# Calliope_mini_rev2_0.net
KiCad netlist of a schematic drawn in EAGLE
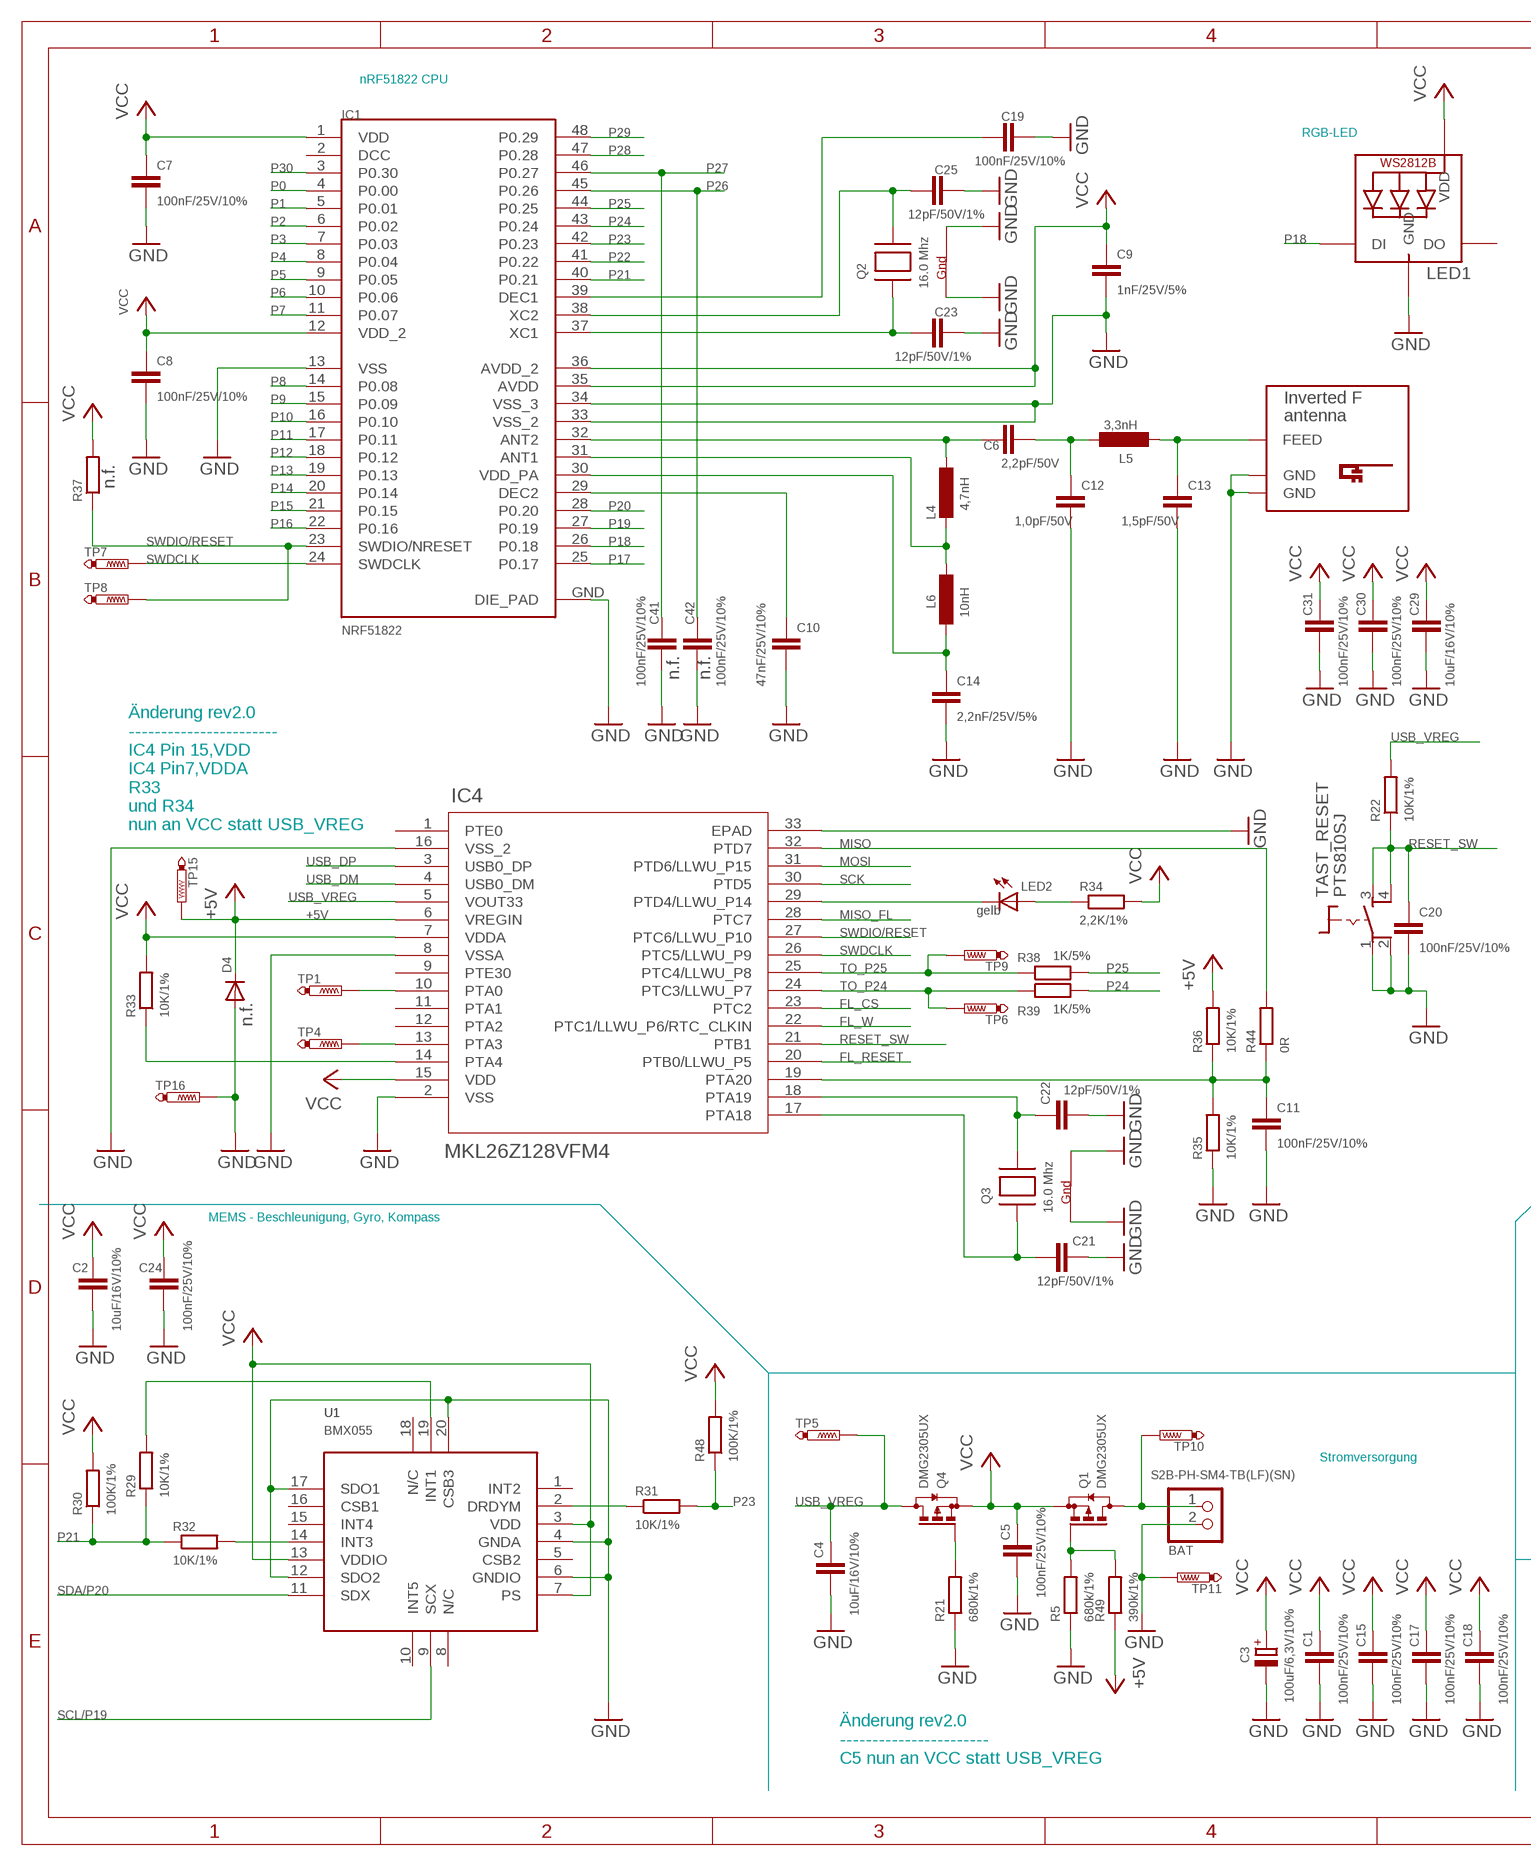
[diagram p0: schematic, sheet 1, part 1 of 2]
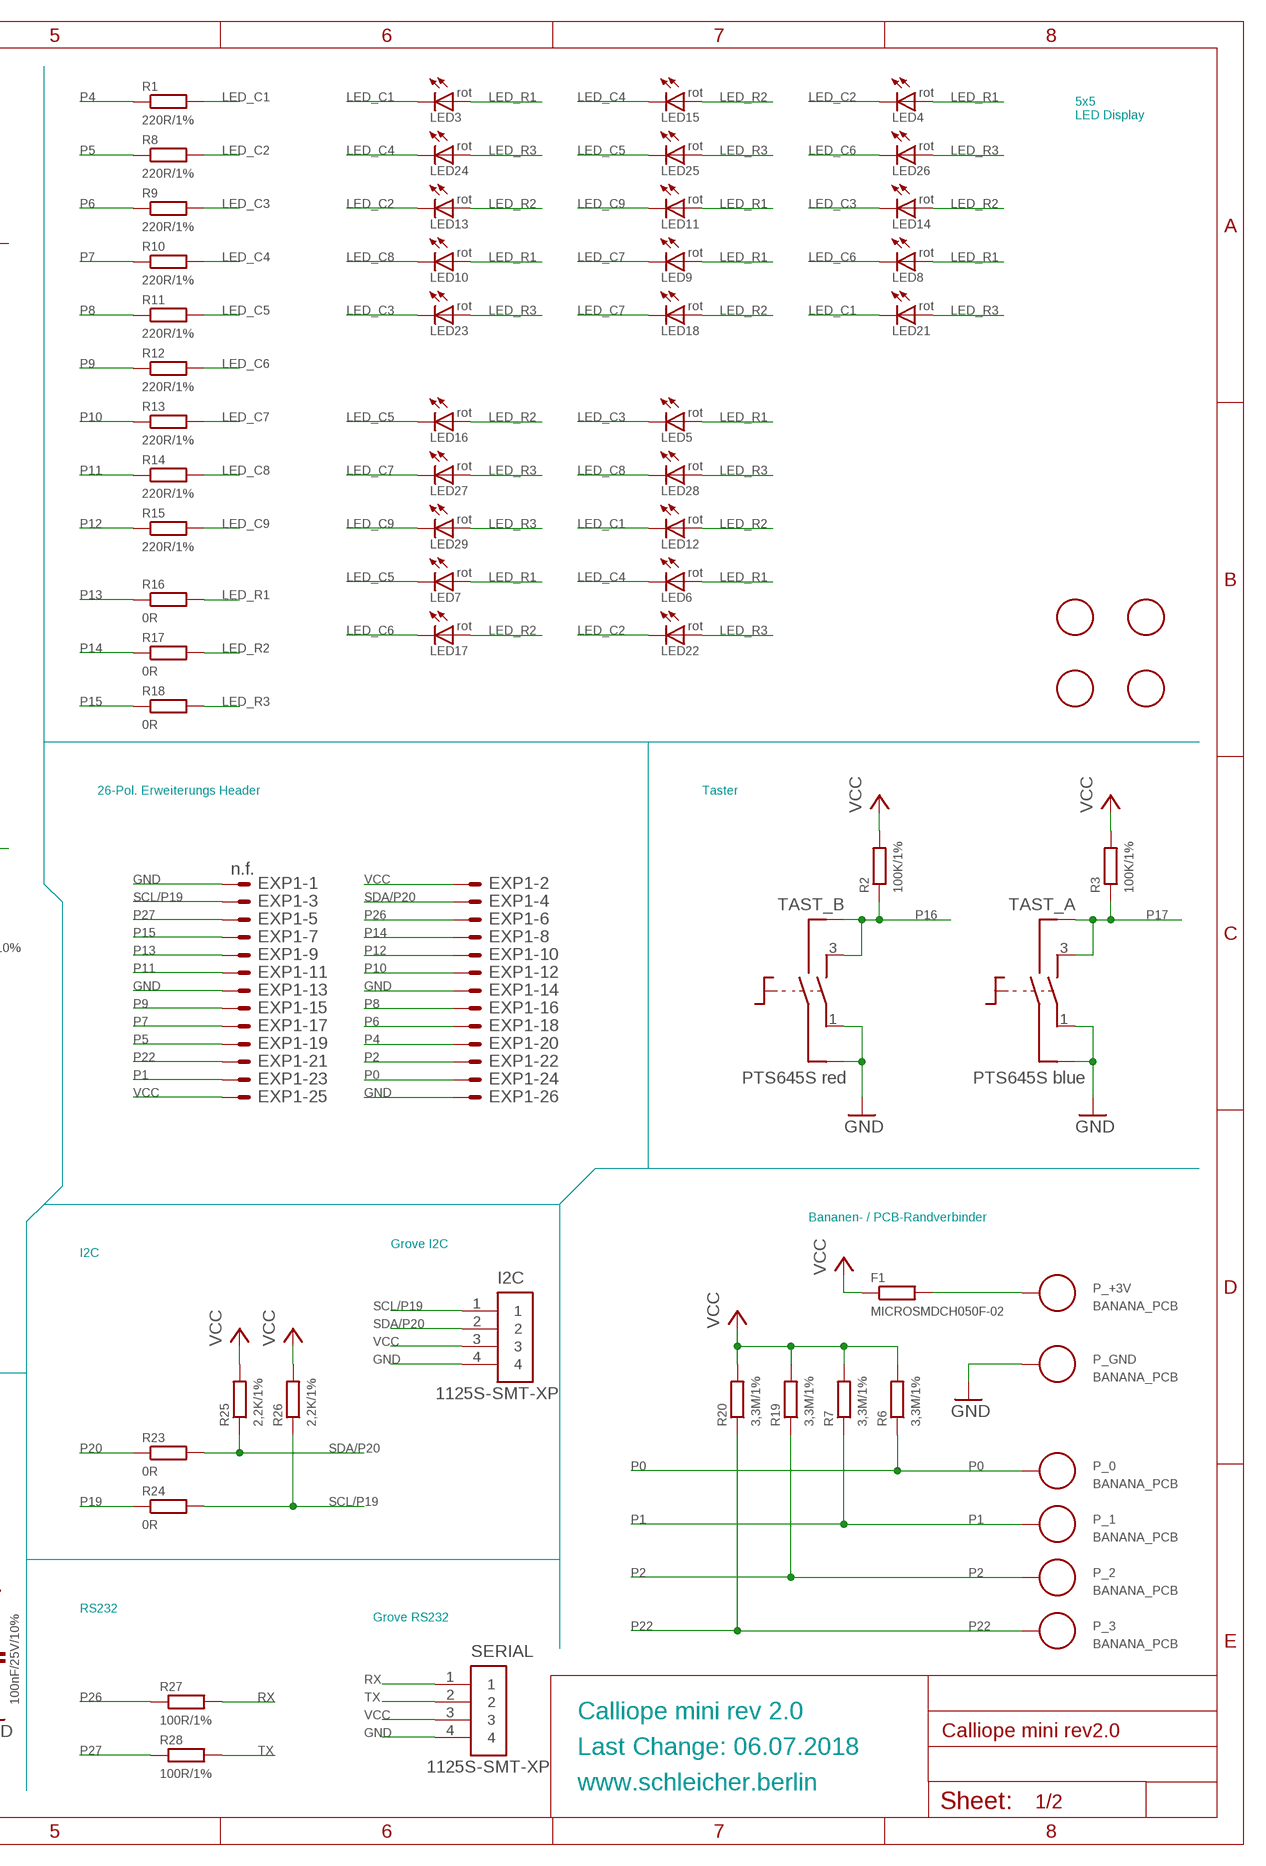
[diagram p1: schematic, sheet 1, part 2 of 2]
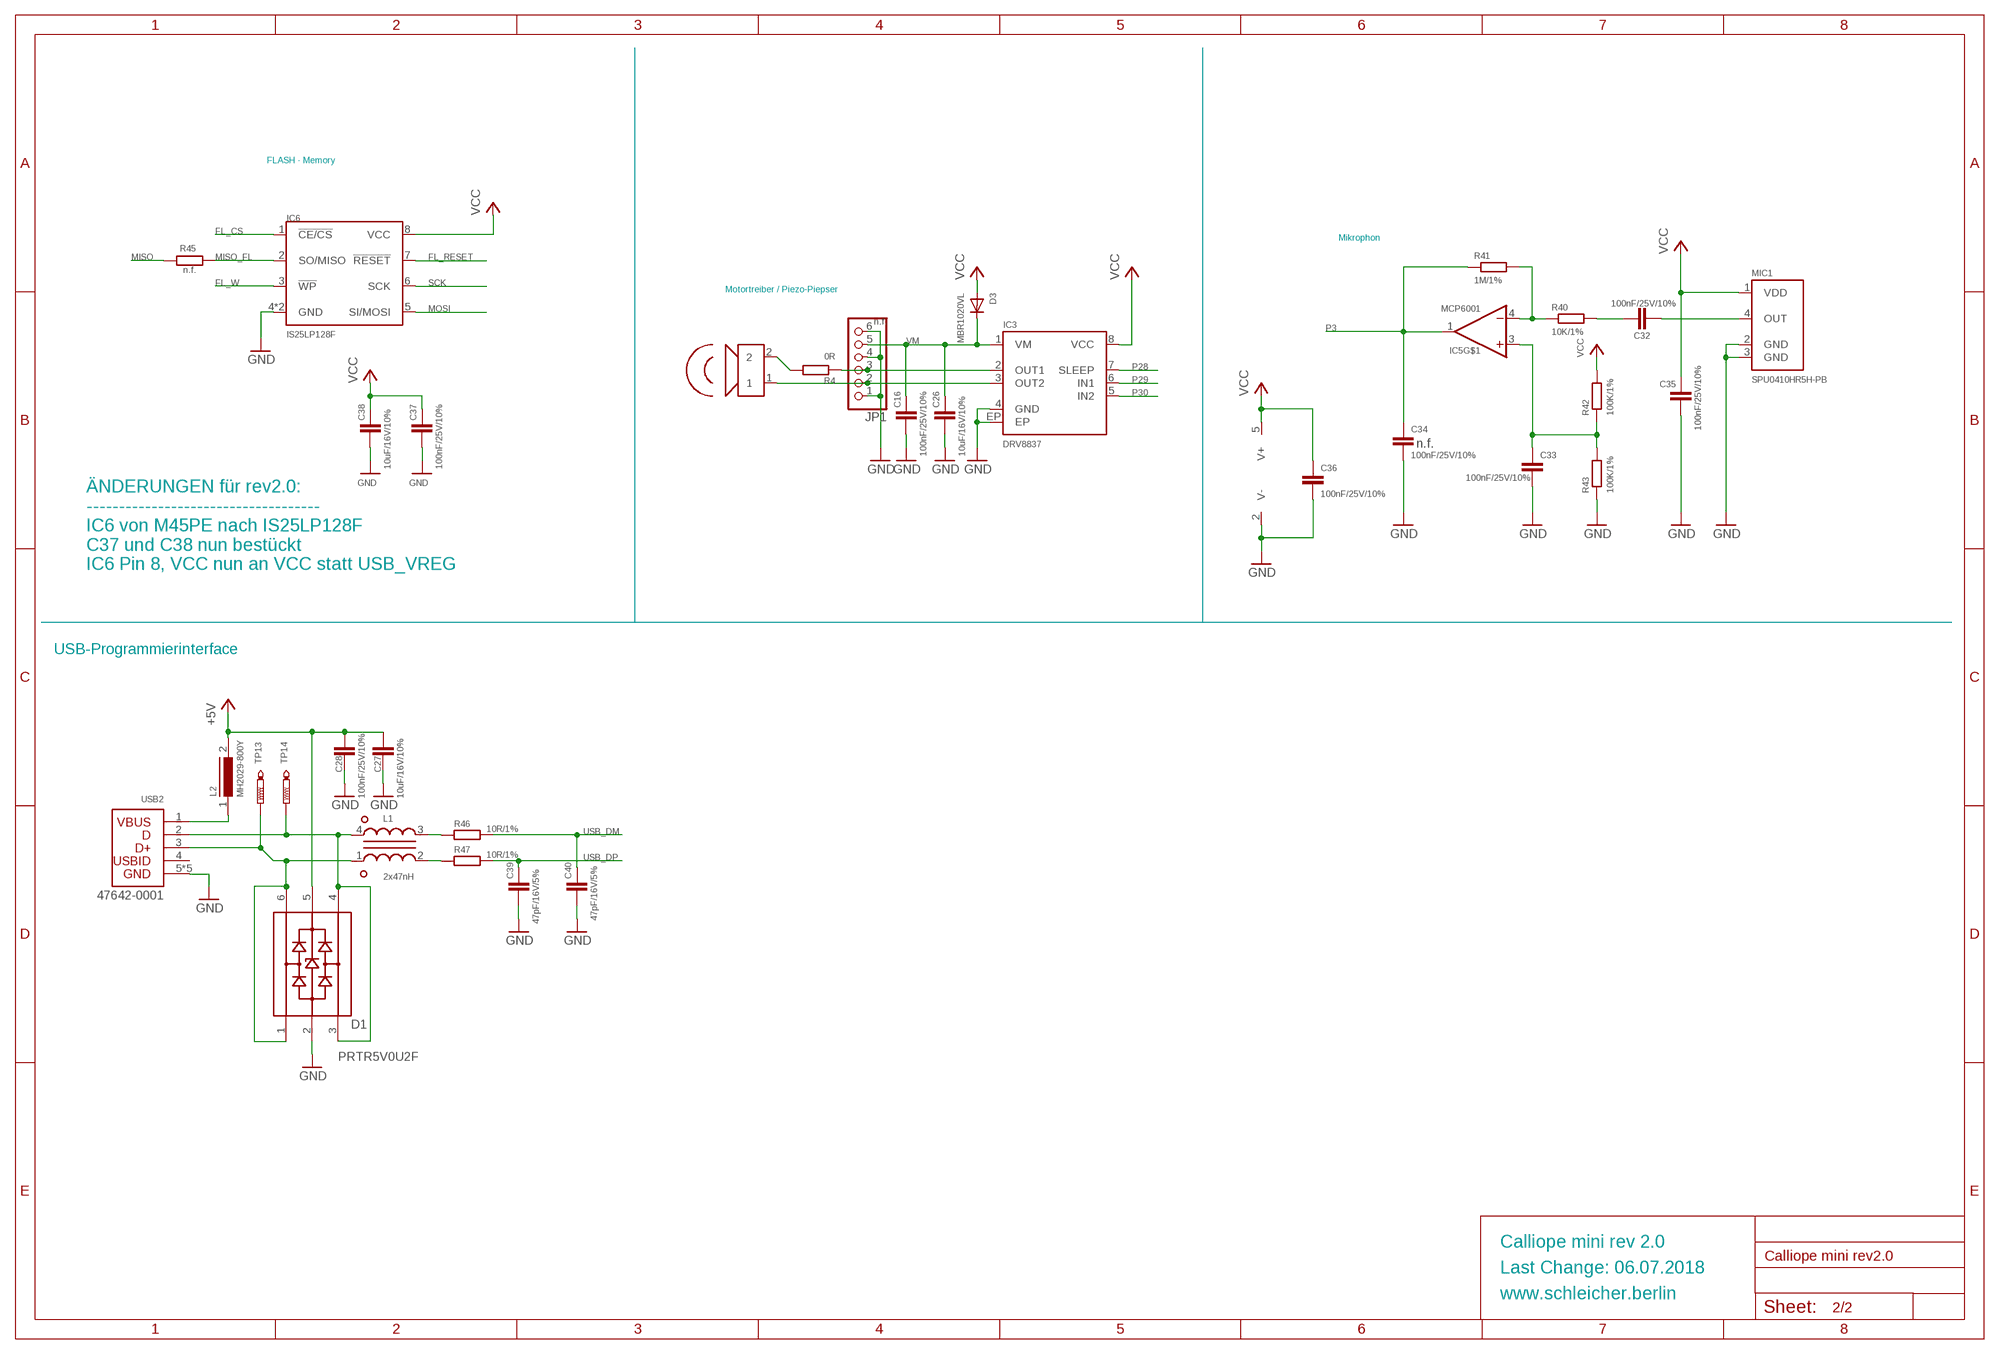
[diagram p2: schematic, sheet 2]

(export (version "E")
  (design (tool "Eeschema 10.0.6"))
  (components
    (comp (ref "BAT")
      (value "S2B-PH-SM4-TB(LF)(SN)")
      (footprint "eagle-import:JST-PH-2-SMT-RA")
      (libsource (lib "eagle-import") (part "JST_2PIN-SMT-RA"))
    )
    (comp (ref "C1")
      (value "100nF/25V/10%")
      (footprint "eagle-import:0402")
      (libsource (lib "eagle-import") (part "C-EU0402"))
    )
    (comp (ref "C2")
      (value "10uF/16V/10%")
      (footprint "eagle-import:0603")
      (libsource (lib "eagle-import") (part "C-EU0603"))
    )
    (comp (ref "C3")
      (value "100uF/6,3V/10%")
      (footprint "eagle-import:D_7343-31R")
      (libsource (lib "eagle-import") (part "CPOL-EUD/7343-31R"))
    )
    (comp (ref "C4")
      (value "10uF/16V/10%")
      (footprint "eagle-import:0603")
      (libsource (lib "eagle-import") (part "C-EU0603"))
    )
    (comp (ref "C5")
      (value "100nF/25V/10%")
      (footprint "eagle-import:0402")
      (libsource (lib "eagle-import") (part "C-EU0402"))
    )
    (comp (ref "C6")
      (value "2,2pF/50V")
      (footprint "eagle-import:0402")
      (libsource (lib "eagle-import") (part "C-EU0402"))
    )
    (comp (ref "C7")
      (value "100nF/25V/10%")
      (footprint "eagle-import:0402")
      (libsource (lib "eagle-import") (part "C-EU0402"))
    )
    (comp (ref "C8")
      (value "100nF/25V/10%")
      (footprint "eagle-import:0402")
      (libsource (lib "eagle-import") (part "C-EU0402"))
    )
    (comp (ref "C9")
      (value "1nF/25V/5%")
      (footprint "eagle-import:0402")
      (libsource (lib "eagle-import") (part "C-EU0402"))
    )
    (comp (ref "C10")
      (value "47nF/25V/10%")
      (footprint "eagle-import:0402")
      (libsource (lib "eagle-import") (part "C-EU0402"))
    )
    (comp (ref "C11")
      (value "100nF/25V/10%")
      (footprint "eagle-import:0402")
      (libsource (lib "eagle-import") (part "C-EU0402"))
    )
    (comp (ref "C12")
      (value "1,0pF/50V")
      (footprint "eagle-import:0402")
      (libsource (lib "eagle-import") (part "C-EU0402"))
    )
    (comp (ref "C13")
      (value "1,5pF/50V")
      (footprint "eagle-import:0402")
      (libsource (lib "eagle-import") (part "C-EU0402"))
    )
    (comp (ref "C14")
      (value "2,2nF/25V/5%")
      (footprint "eagle-import:0402")
      (libsource (lib "eagle-import") (part "C-EU0402"))
    )
    (comp (ref "C15")
      (value "100nF/25V/10%")
      (footprint "eagle-import:0402")
      (libsource (lib "eagle-import") (part "C-EU0402"))
    )
    (comp (ref "C17")
      (value "100nF/25V/10%")
      (footprint "eagle-import:0402")
      (libsource (lib "eagle-import") (part "C-EU0402"))
    )
    (comp (ref "C18")
      (value "100nF/25V/10%")
      (footprint "eagle-import:0402")
      (libsource (lib "eagle-import") (part "C-EU0402"))
    )
    (comp (ref "C19")
      (value "100nF/25V/10%")
      (footprint "eagle-import:0402")
      (libsource (lib "eagle-import") (part "C-EU0402"))
    )
    (comp (ref "C20")
      (value "100nF/25V/10%")
      (footprint "eagle-import:0402")
      (libsource (lib "eagle-import") (part "C-EU0402"))
    )
    (comp (ref "C21")
      (value "12pF/50V/1%")
      (footprint "eagle-import:0402")
      (libsource (lib "eagle-import") (part "C-EU0402"))
    )
    (comp (ref "C22")
      (value "12pF/50V/1%")
      (footprint "eagle-import:0402")
      (libsource (lib "eagle-import") (part "C-EU0402"))
    )
    (comp (ref "C23")
      (value "12pF/50V/1%")
      (footprint "eagle-import:0402")
      (libsource (lib "eagle-import") (part "C-EU0402"))
    )
    (comp (ref "C24")
      (value "100nF/25V/10%")
      (footprint "eagle-import:0402")
      (libsource (lib "eagle-import") (part "C-EU0402"))
    )
    (comp (ref "C25")
      (value "12pF/50V/1%")
      (footprint "eagle-import:0402")
      (libsource (lib "eagle-import") (part "C-EU0402"))
    )
    (comp (ref "C29")
      (value "10uF/16V/10%")
      (footprint "eagle-import:0603")
      (libsource (lib "eagle-import") (part "C-EU0603"))
    )
    (comp (ref "C30")
      (value "100nF/25V/10%")
      (footprint "eagle-import:0402")
      (libsource (lib "eagle-import") (part "C-EU0402"))
    )
    (comp (ref "C31")
      (value "100nF/25V/10%")
      (footprint "eagle-import:0402")
      (libsource (lib "eagle-import") (part "C-EU0402"))
    )
    (comp (ref "C41")
      (value "100nF/25V/10%")
      (footprint "eagle-import:0402")
      (fields (field (name "MOUNTING") "n.f."))
      (libsource (lib "eagle-import") (part "C-EU0402"))
    )
    (comp (ref "C42")
      (value "100nF/25V/10%")
      (footprint "eagle-import:0402")
      (fields (field (name "MOUNTING") "n.f."))
      (libsource (lib "eagle-import") (part "C-EU0402"))
    )
    (comp (ref "D4")
      (value "DIODE-SOD323-R")
      (footprint "eagle-import:SOD323-R")
      (fields (field (name "MOUNTING") "n.f."))
      (libsource (lib "eagle-import") (part "DIODE-SOD323-R"))
    )
    (comp (ref "EXP1")
      (value "ML26E")
      (footprint "eagle-import:ML26")
      (fields (field (name "MOUNTING") "n.f."))
      (libsource (lib "eagle-import") (part "ML26?E"))
    )
    (comp (ref "F1")
      (value "MICROSMDCH050F-02")
      (footprint "eagle-import:R1210")
      (libsource (lib "eagle-import") (part "R-EU_R1210"))
    )
    (comp (ref "I2C")
      (value "1125S-SMT-XP")
      (footprint "eagle-import:1125S-SMT-XP")
      (libsource (lib "eagle-import") (part "1125-SMT-XPS"))
    )
    (comp (ref "IC1")
      (value "NRF51822")
      (footprint "eagle-import:QFN48")
      (libsource (lib "eagle-import") (part "NRF51822"))
    )
    (comp (ref "IC4")
      (value "MKL26Z128VFM4")
      (footprint "eagle-import:QFN_32_5X5X0P9")
      (libsource (lib "eagle-import") (part "MKL26Z"))
    )
    (comp (ref "L4")
      (value "4,7nH")
      (footprint "eagle-import:0402")
      (libsource (lib "eagle-import") (part "L-EU0402"))
    )
    (comp (ref "L5")
      (value "3,3nH")
      (footprint "eagle-import:0402")
      (libsource (lib "eagle-import") (part "L-EU0402"))
    )
    (comp (ref "L6")
      (value "10nH")
      (footprint "eagle-import:0402")
      (libsource (lib "eagle-import") (part "L-EU0402"))
    )
    (comp (ref "LED1")
      (value "SK6812MINI")
      (footprint "eagle-import:LED3535")
      (libsource (lib "eagle-import") (part "WS2812B3535"))
    )
    (comp (ref "LED2")
      (value "gelb")
      (footprint "eagle-import:CHIPLED_0603")
      (libsource (lib "eagle-import") (part "LEDCHIPLED_0603"))
    )
    (comp (ref "LED3")
      (value "rot")
      (footprint "eagle-import:CHIPLED_0603")
      (libsource (lib "eagle-import") (part "LEDCHIPLED_0603"))
    )
    (comp (ref "LED4")
      (value "rot")
      (footprint "eagle-import:CHIPLED_0603")
      (libsource (lib "eagle-import") (part "LEDCHIPLED_0603"))
    )
    (comp (ref "LED5")
      (value "rot")
      (footprint "eagle-import:CHIPLED_0603")
      (libsource (lib "eagle-import") (part "LEDCHIPLED_0603"))
    )
    (comp (ref "LED6")
      (value "rot")
      (footprint "eagle-import:CHIPLED_0603")
      (libsource (lib "eagle-import") (part "LEDCHIPLED_0603"))
    )
    (comp (ref "LED7")
      (value "rot")
      (footprint "eagle-import:CHIPLED_0603")
      (libsource (lib "eagle-import") (part "LEDCHIPLED_0603"))
    )
    (comp (ref "LED8")
      (value "rot")
      (footprint "eagle-import:CHIPLED_0603")
      (libsource (lib "eagle-import") (part "LEDCHIPLED_0603"))
    )
    (comp (ref "LED9")
      (value "rot")
      (footprint "eagle-import:CHIPLED_0603")
      (libsource (lib "eagle-import") (part "LEDCHIPLED_0603"))
    )
    (comp (ref "LED10")
      (value "rot")
      (footprint "eagle-import:CHIPLED_0603")
      (libsource (lib "eagle-import") (part "LEDCHIPLED_0603"))
    )
    (comp (ref "LED11")
      (value "rot")
      (footprint "eagle-import:CHIPLED_0603")
      (libsource (lib "eagle-import") (part "LEDCHIPLED_0603"))
    )
    (comp (ref "LED12")
      (value "rot")
      (footprint "eagle-import:CHIPLED_0603")
      (libsource (lib "eagle-import") (part "LEDCHIPLED_0603"))
    )
    (comp (ref "LED13")
      (value "rot")
      (footprint "eagle-import:CHIPLED_0603")
      (libsource (lib "eagle-import") (part "LEDCHIPLED_0603"))
    )
    (comp (ref "LED14")
      (value "rot")
      (footprint "eagle-import:CHIPLED_0603")
      (libsource (lib "eagle-import") (part "LEDCHIPLED_0603"))
    )
    (comp (ref "LED15")
      (value "rot")
      (footprint "eagle-import:CHIPLED_0603")
      (libsource (lib "eagle-import") (part "LEDCHIPLED_0603"))
    )
    (comp (ref "LED16")
      (value "rot")
      (footprint "eagle-import:CHIPLED_0603")
      (libsource (lib "eagle-import") (part "LEDCHIPLED_0603"))
    )
    (comp (ref "LED17")
      (value "rot")
      (footprint "eagle-import:CHIPLED_0603")
      (libsource (lib "eagle-import") (part "LEDCHIPLED_0603"))
    )
    (comp (ref "LED18")
      (value "rot")
      (footprint "eagle-import:CHIPLED_0603")
      (libsource (lib "eagle-import") (part "LEDCHIPLED_0603"))
    )
    (comp (ref "LED21")
      (value "rot")
      (footprint "eagle-import:CHIPLED_0603")
      (libsource (lib "eagle-import") (part "LEDCHIPLED_0603"))
    )
    (comp (ref "LED22")
      (value "rot")
      (footprint "eagle-import:CHIPLED_0603")
      (libsource (lib "eagle-import") (part "LEDCHIPLED_0603"))
    )
    (comp (ref "LED23")
      (value "rot")
      (footprint "eagle-import:CHIPLED_0603")
      (libsource (lib "eagle-import") (part "LEDCHIPLED_0603"))
    )
    (comp (ref "LED24")
      (value "rot")
      (footprint "eagle-import:CHIPLED_0603")
      (libsource (lib "eagle-import") (part "LEDCHIPLED_0603"))
    )
    (comp (ref "LED25")
      (value "rot")
      (footprint "eagle-import:CHIPLED_0603")
      (libsource (lib "eagle-import") (part "LEDCHIPLED_0603"))
    )
    (comp (ref "LED26")
      (value "rot")
      (footprint "eagle-import:CHIPLED_0603")
      (libsource (lib "eagle-import") (part "LEDCHIPLED_0603"))
    )
    (comp (ref "LED27")
      (value "rot")
      (footprint "eagle-import:CHIPLED_0603")
      (libsource (lib "eagle-import") (part "LEDCHIPLED_0603"))
    )
    (comp (ref "LED28")
      (value "rot")
      (footprint "eagle-import:CHIPLED_0603")
      (libsource (lib "eagle-import") (part "LEDCHIPLED_0603"))
    )
    (comp (ref "LED29")
      (value "rot")
      (footprint "eagle-import:CHIPLED_0603")
      (libsource (lib "eagle-import") (part "LEDCHIPLED_0603"))
    )
    (comp (ref "P_+3V")
      (value "BANANA_PCB")
      (footprint "eagle-import:BANANA_REC")
      (libsource (lib "eagle-import") (part "BANANA_PCB"))
    )
    (comp (ref "P_0")
      (value "BANANA_PCB")
      (footprint "eagle-import:BANANA_REC")
      (libsource (lib "eagle-import") (part "BANANA_PCB"))
    )
    (comp (ref "P_1")
      (value "BANANA_PCB")
      (footprint "eagle-import:BANANA_REC")
      (libsource (lib "eagle-import") (part "BANANA_PCB"))
    )
    (comp (ref "P_2")
      (value "BANANA_PCB")
      (footprint "eagle-import:BANANA_REC")
      (libsource (lib "eagle-import") (part "BANANA_PCB"))
    )
    (comp (ref "P_3")
      (value "BANANA_PCB")
      (footprint "eagle-import:BANANA_REC")
      (libsource (lib "eagle-import") (part "BANANA_PCB"))
    )
    (comp (ref "P_GND")
      (value "BANANA_PCB")
      (footprint "eagle-import:BANANA_REC")
      (libsource (lib "eagle-import") (part "BANANA_PCB"))
    )
    (comp (ref "Q1")
      (value "DMG2305UX")
      (footprint "eagle-import:SOT23")
      (libsource (lib "eagle-import") (part "BSS84"))
    )
    (comp (ref "Q2")
      (value "16.0 Mhz")
      (footprint "eagle-import:NX3225")
      (libsource (lib "eagle-import") (part "XTAL-4-3225"))
    )
    (comp (ref "Q3")
      (value "16.0 Mhz")
      (footprint "eagle-import:NX3225")
      (libsource (lib "eagle-import") (part "XTAL-4-3225"))
    )
    (comp (ref "Q4")
      (value "DMG2305UX")
      (footprint "eagle-import:SOT23")
      (libsource (lib "eagle-import") (part "BSS84"))
    )
    (comp (ref "R1")
      (value "220R/1%")
      (footprint "eagle-import:0402")
      (libsource (lib "eagle-import") (part "R-EU_0402"))
    )
    (comp (ref "R2")
      (value "100K/1%")
      (footprint "eagle-import:0402")
      (libsource (lib "eagle-import") (part "R-EU_0402"))
    )
    (comp (ref "R3")
      (value "100K/1%")
      (footprint "eagle-import:0402")
      (libsource (lib "eagle-import") (part "R-EU_0402"))
    )
    (comp (ref "R5")
      (value "680k/1%")
      (footprint "eagle-import:0402")
      (libsource (lib "eagle-import") (part "R-EU_0402"))
    )
    (comp (ref "R6")
      (value "3,3M/1%")
      (footprint "eagle-import:0402")
      (libsource (lib "eagle-import") (part "R-EU_0402"))
    )
    (comp (ref "R7")
      (value "3,3M/1%")
      (footprint "eagle-import:0402")
      (libsource (lib "eagle-import") (part "R-EU_0402"))
    )
    (comp (ref "R8")
      (value "220R/1%")
      (footprint "eagle-import:0402")
      (libsource (lib "eagle-import") (part "R-EU_0402"))
    )
    (comp (ref "R9")
      (value "220R/1%")
      (footprint "eagle-import:0402")
      (libsource (lib "eagle-import") (part "R-EU_0402"))
    )
    (comp (ref "R10")
      (value "220R/1%")
      (footprint "eagle-import:0402")
      (libsource (lib "eagle-import") (part "R-EU_0402"))
    )
    (comp (ref "R11")
      (value "220R/1%")
      (footprint "eagle-import:0402")
      (libsource (lib "eagle-import") (part "R-EU_0402"))
    )
    (comp (ref "R12")
      (value "220R/1%")
      (footprint "eagle-import:0402")
      (libsource (lib "eagle-import") (part "R-EU_0402"))
    )
    (comp (ref "R13")
      (value "220R/1%")
      (footprint "eagle-import:0402")
      (libsource (lib "eagle-import") (part "R-EU_0402"))
    )
    (comp (ref "R14")
      (value "220R/1%")
      (footprint "eagle-import:0402")
      (libsource (lib "eagle-import") (part "R-EU_0402"))
    )
    (comp (ref "R15")
      (value "220R/1%")
      (footprint "eagle-import:0402")
      (libsource (lib "eagle-import") (part "R-EU_0402"))
    )
    (comp (ref "R16")
      (value "0R")
      (footprint "eagle-import:0402")
      (libsource (lib "eagle-import") (part "R-EU_0402"))
    )
    (comp (ref "R17")
      (value "0R")
      (footprint "eagle-import:0402")
      (libsource (lib "eagle-import") (part "R-EU_0402"))
    )
    (comp (ref "R18")
      (value "0R")
      (footprint "eagle-import:0402")
      (libsource (lib "eagle-import") (part "R-EU_0402"))
    )
    (comp (ref "R19")
      (value "3,3M/1%")
      (footprint "eagle-import:0402")
      (libsource (lib "eagle-import") (part "R-EU_0402"))
    )
    (comp (ref "R20")
      (value "3,3M/1%")
      (footprint "eagle-import:0402")
      (libsource (lib "eagle-import") (part "R-EU_0402"))
    )
    (comp (ref "R21")
      (value "680k/1%")
      (footprint "eagle-import:0402")
      (libsource (lib "eagle-import") (part "R-EU_0402"))
    )
    (comp (ref "R22")
      (value "10K/1%")
      (footprint "eagle-import:0402")
      (libsource (lib "eagle-import") (part "R-EU_0402"))
    )
    (comp (ref "R23")
      (value "0R")
      (footprint "eagle-import:0402")
      (libsource (lib "eagle-import") (part "R-EU_0402"))
    )
    (comp (ref "R24")
      (value "0R")
      (footprint "eagle-import:0402")
      (libsource (lib "eagle-import") (part "R-EU_0402"))
    )
    (comp (ref "R25")
      (value "2,2K/1%")
      (footprint "eagle-import:0402")
      (libsource (lib "eagle-import") (part "R-EU_0402"))
    )
    (comp (ref "R26")
      (value "2,2K/1%")
      (footprint "eagle-import:0402")
      (libsource (lib "eagle-import") (part "R-EU_0402"))
    )
    (comp (ref "R27")
      (value "100R/1%")
      (footprint "eagle-import:0402")
      (libsource (lib "eagle-import") (part "R-EU_0402"))
    )
    (comp (ref "R28")
      (value "100R/1%")
      (footprint "eagle-import:0402")
      (libsource (lib "eagle-import") (part "R-EU_0402"))
    )
    (comp (ref "R29")
      (value "10K/1%")
      (footprint "eagle-import:0402")
      (libsource (lib "eagle-import") (part "R-EU_0402"))
    )
    (comp (ref "R30")
      (value "100K/1%")
      (footprint "eagle-import:0402")
      (libsource (lib "eagle-import") (part "R-EU_0402"))
    )
    (comp (ref "R31")
      (value "10K/1%")
      (footprint "eagle-import:0402")
      (libsource (lib "eagle-import") (part "R-EU_0402"))
    )
    (comp (ref "R32")
      (value "10K/1%")
      (footprint "eagle-import:0402")
      (libsource (lib "eagle-import") (part "R-EU_0402"))
    )
    (comp (ref "R33")
      (value "10K/1%")
      (footprint "eagle-import:0402")
      (libsource (lib "eagle-import") (part "R-EU_0402"))
    )
    (comp (ref "R34")
      (value "2,2K/1%")
      (footprint "eagle-import:0402")
      (libsource (lib "eagle-import") (part "R-EU_0402"))
    )
    (comp (ref "R35")
      (value "10K/1%")
      (footprint "eagle-import:0402")
      (libsource (lib "eagle-import") (part "R-EU_0402"))
    )
    (comp (ref "R36")
      (value "10K/1%")
      (footprint "eagle-import:0402")
      (libsource (lib "eagle-import") (part "R-EU_0402"))
    )
    (comp (ref "R37")
      (value "R-EU_0402")
      (footprint "eagle-import:0402")
      (fields (field (name "MOUNTING") "n.f."))
      (libsource (lib "eagle-import") (part "R-EU_0402"))
    )
    (comp (ref "R38")
      (value "1K/5%")
      (footprint "eagle-import:0402")
      (libsource (lib "eagle-import") (part "R-EU_0402"))
    )
    (comp (ref "R39")
      (value "1K/5%")
      (footprint "eagle-import:0402")
      (libsource (lib "eagle-import") (part "R-EU_0402"))
    )
    (comp (ref "R44")
      (value "0R")
      (footprint "eagle-import:0402")
      (libsource (lib "eagle-import") (part "R-EU_0402"))
    )
    (comp (ref "R48")
      (value "100K/1%")
      (footprint "eagle-import:0402")
      (libsource (lib "eagle-import") (part "R-EU_0402"))
    )
    (comp (ref "R49")
      (value "390k/1%")
      (footprint "eagle-import:0402")
      (libsource (lib "eagle-import") (part "R-EU_0402"))
    )
    (comp (ref "SERIAL")
      (value "1125S-SMT-XP")
      (footprint "eagle-import:1125S-SMT-XP")
      (libsource (lib "eagle-import") (part "1125-SMT-XPS"))
    )
    (comp (ref "TAST_A")
      (value "PTS645S blue")
      (footprint "eagle-import:PTS645S")
      (libsource (lib "eagle-import") (part "PTS645S"))
    )
    (comp (ref "TAST_B")
      (value "PTS645S red")
      (footprint "eagle-import:PTS645S")
      (libsource (lib "eagle-import") (part "PTS645S"))
    )
    (comp (ref "TAST_RESET")
      (value "PTS810SJ")
      (footprint "eagle-import:PTS810")
      (libsource (lib "eagle-import") (part "PTS810SJ"))
    )
    (comp (ref "TP1")
      (value "PTR1B1,27")
      (footprint "eagle-import:B1,27")
      (libsource (lib "eagle-import") (part "PTR1B1,27"))
    )
    (comp (ref "TP4")
      (value "PTR1B1,27")
      (footprint "eagle-import:B1,27")
      (libsource (lib "eagle-import") (part "PTR1B1,27"))
    )
    (comp (ref "TP5")
      (value "PTR1B1,27")
      (footprint "eagle-import:B1,27")
      (libsource (lib "eagle-import") (part "PTR1B1,27"))
    )
    (comp (ref "TP6")
      (value "PTR1B1,27")
      (footprint "eagle-import:B1,27")
      (libsource (lib "eagle-import") (part "PTR1B1,27"))
    )
    (comp (ref "TP7")
      (value "PTR1B1,27")
      (footprint "eagle-import:B1,27")
      (libsource (lib "eagle-import") (part "PTR1B1,27"))
    )
    (comp (ref "TP8")
      (value "PTR1B1,27")
      (footprint "eagle-import:B1,27")
      (libsource (lib "eagle-import") (part "PTR1B1,27"))
    )
    (comp (ref "TP9")
      (value "PTR1B1,27")
      (footprint "eagle-import:B1,27")
      (libsource (lib "eagle-import") (part "PTR1B1,27"))
    )
    (comp (ref "TP10")
      (value "PTR1B1,27")
      (footprint "eagle-import:B1,27")
      (libsource (lib "eagle-import") (part "PTR1B1,27"))
    )
    (comp (ref "TP11")
      (value "PTR1B1,27")
      (footprint "eagle-import:B1,27")
      (libsource (lib "eagle-import") (part "PTR1B1,27"))
    )
    (comp (ref "TP15")
      (value "PTR1B1,27")
      (footprint "eagle-import:B1,27")
      (libsource (lib "eagle-import") (part "PTR1B1,27"))
    )
    (comp (ref "TP16")
      (value "PTR1B1,27")
      (footprint "eagle-import:B1,27")
      (libsource (lib "eagle-import") (part "PTR1B1,27"))
    )
    (comp (ref "U$2")
      (value "INVERTED_F_ANTENNA")
      (footprint "eagle-import:DN0007+0_MIRROR")
      (libsource (lib "eagle-import") (part "INVERTED_F_ANTENNA"))
    )
    (comp (ref "U$5")
      (value "FIDUCIAL")
      (footprint "eagle-import:FIDUCIAL_1MM")
      (libsource (lib "eagle-import") (part "FIDUCIAL"))
    )
    (comp (ref "U$6")
      (value "FIDUCIAL")
      (footprint "eagle-import:FIDUCIAL_1MM")
      (libsource (lib "eagle-import") (part "FIDUCIAL"))
    )
    (comp (ref "U$7")
      (value "FIDUCIAL")
      (footprint "eagle-import:FIDUCIAL_1MM")
      (libsource (lib "eagle-import") (part "FIDUCIAL"))
    )
    (comp (ref "U$8")
      (value "FIDUCIAL")
      (footprint "eagle-import:FIDUCIAL_1MM")
      (libsource (lib "eagle-import") (part "FIDUCIAL"))
    )
    (comp (ref "U1")
      (value "BMX055")
      (footprint "eagle-import:BMX055")
      (libsource (lib "eagle-import") (part "BMX055"))
    )
    (comp (ref "C16")
      (value "100nF/25V/10%")
      (footprint "eagle-import:0402")
      (libsource (lib "eagle-import") (part "C-EU0402"))
    )
    (comp (ref "C26")
      (value "10uF/16V/10%")
      (footprint "eagle-import:0603")
      (libsource (lib "eagle-import") (part "C-EU0603"))
    )
    (comp (ref "C27")
      (value "10uF/16V/10%")
      (footprint "eagle-import:0603")
      (libsource (lib "eagle-import") (part "C-EU0603"))
    )
    (comp (ref "C28")
      (value "100nF/25V/10%")
      (footprint "eagle-import:0402")
      (libsource (lib "eagle-import") (part "C-EU0402"))
    )
    (comp (ref "C32")
      (value "100nF/25V/10%")
      (footprint "eagle-import:0402")
      (libsource (lib "eagle-import") (part "C-EU0402"))
    )
    (comp (ref "C33")
      (value "100nF/25V/10%")
      (footprint "eagle-import:0402")
      (libsource (lib "eagle-import") (part "C-EU0402"))
    )
    (comp (ref "C34")
      (value "100nF/25V/10%")
      (footprint "eagle-import:0402")
      (fields (field (name "MOUNTING") "n.f."))
      (libsource (lib "eagle-import") (part "C-EU0402"))
    )
    (comp (ref "C35")
      (value "100nF/25V/10%")
      (footprint "eagle-import:0402")
      (libsource (lib "eagle-import") (part "C-EU0402"))
    )
    (comp (ref "C36")
      (value "100nF/25V/10%")
      (footprint "eagle-import:0402")
      (libsource (lib "eagle-import") (part "C-EU0402"))
    )
    (comp (ref "C37")
      (value "100nF/25V/10%")
      (footprint "eagle-import:0402")
      (libsource (lib "eagle-import") (part "C-EU0402"))
    )
    (comp (ref "C38")
      (value "10uF/16V/10%")
      (footprint "eagle-import:0603")
      (libsource (lib "eagle-import") (part "C-EU0603"))
    )
    (comp (ref "C39")
      (value "47pF/16V/5%")
      (footprint "eagle-import:0402")
      (libsource (lib "eagle-import") (part "C-EU0402"))
    )
    (comp (ref "C40")
      (value "47pF/16V/5%")
      (footprint "eagle-import:0402")
      (libsource (lib "eagle-import") (part "C-EU0402"))
    )
    (comp (ref "D1")
      (value "PRTR5V0U2F")
      (footprint "eagle-import:SOT886")
      (libsource (lib "eagle-import") (part "PRTR5V0U2F"))
    )
    (comp (ref "D3")
      (value "MBR1020VL")
      (footprint "eagle-import:SOD-123FL")
      (libsource (lib "eagle-import") (part "DIODE_SOD-123FL"))
    )
    (comp (ref "IC3")
      (value "DRV8837")
      (footprint "eagle-import:WSON8")
      (libsource (lib "eagle-import") (part "DRV8837"))
    )
    (comp (ref "IC5")
      (value "MCP6001")
      (footprint "eagle-import:SOT23-5")
      (libsource (lib "eagle-import") (part "OPAMP_SINGLESOT23-5"))
    )
    (comp (ref "IC6")
      (value "IS25LP128F")
      (footprint "eagle-import:VQFN8_6X5")
      (libsource (lib "eagle-import") (part "IS25LP128F"))
    )
    (comp (ref "JP1")
      (value "PINHD-1X6-OFF")
      (footprint "eagle-import:1X06-OFF")
      (libsource (lib "eagle-import") (part "PINHD-1X6-OFF"))
    )
    (comp (ref "L1")
      (value "2x47nH")
      (footprint "eagle-import:USB_2.0_FILTER_0805")
      (libsource (lib "eagle-import") (part "0805USB-901MLC"))
    )
    (comp (ref "L2")
      (value "MH2029-800Y")
      (footprint "eagle-import:FERRIT_0805")
      (fields (field (name "TOLERANCE") "+-25%"))
      (libsource (lib "eagle-import") (part "MH2029-Y800"))
    )
    (comp (ref "MIC1")
      (value "SPU0410HR5H-PB")
      (footprint "eagle-import:SPU0410HR5H-PB")
      (libsource (lib "eagle-import") (part "SPU0410HR5H-PB"))
    )
    (comp (ref "R4")
      (value "0R")
      (footprint "eagle-import:0402")
      (libsource (lib "eagle-import") (part "R-EU_0402"))
    )
    (comp (ref "R40")
      (value "10K/1%")
      (footprint "eagle-import:0402")
      (libsource (lib "eagle-import") (part "R-EU_0402"))
    )
    (comp (ref "R41")
      (value "1M/1%")
      (footprint "eagle-import:0402")
      (libsource (lib "eagle-import") (part "R-EU_0402"))
    )
    (comp (ref "R42")
      (value "100K/1%")
      (footprint "eagle-import:0402")
      (libsource (lib "eagle-import") (part "R-EU_0402"))
    )
    (comp (ref "R43")
      (value "100K/1%")
      (footprint "eagle-import:0402")
      (libsource (lib "eagle-import") (part "R-EU_0402"))
    )
    (comp (ref "R45")
      (value "100R/1%")
      (footprint "eagle-import:0402")
      (fields (field (name "MOUNTING") "n.f."))
      (libsource (lib "eagle-import") (part "R-EU_0402"))
    )
    (comp (ref "R46")
      (value "10R/1%")
      (footprint "eagle-import:R0603")
      (libsource (lib "eagle-import") (part "resistor_R-EU_R0603"))
    )
    (comp (ref "R47")
      (value "10R/1%")
      (footprint "eagle-import:R0603")
      (libsource (lib "eagle-import") (part "resistor_R-EU_R0603"))
    )
    (comp (ref "SPK1")
      (value "PKMCS0909E4000-R1")
      (footprint "eagle-import:PKMCS")
      (libsource (lib "eagle-import") (part "PKMCS0909E4000-R1"))
    )
    (comp (ref "TP13")
      (value "PTR1B1,27")
      (footprint "eagle-import:B1,27")
      (libsource (lib "eagle-import") (part "PTR1B1,27"))
    )
    (comp (ref "TP14")
      (value "PTR1B1,27")
      (footprint "eagle-import:B1,27")
      (libsource (lib "eagle-import") (part "PTR1B1,27"))
    )
    (comp (ref "USB2")
      (value "47642-0001")
      (footprint "eagle-import:47642-0001")
      (libsource (lib "eagle-import") (part "47642-0001"))
    )
  )
  (nets
    (net (code "1") (name "+5V") (class "Default")
      (node (ref "C27") (pin "1") (pinfunction "1_1") (pintype "passive"))
      (node (ref "C28") (pin "1") (pinfunction "1_1") (pintype "passive"))
      (node (ref "D1") (pin "5") (pinfunction "5_5") (pintype "bidirectional"))
      (node (ref "D4") (pin "C") (pinfunction "C_C") (pintype "passive"))
      (node (ref "IC4") (pin "6") (pinfunction "VREGIN_6") (pintype "input"))
      (node (ref "L2") (pin "2") (pinfunction "2_2") (pintype "passive"))
      (node (ref "R36") (pin "2") (pinfunction "2_2") (pintype "passive"))
      (node (ref "R49") (pin "1") (pinfunction "1_1") (pintype "passive"))
      (node (ref "TP15") (pin "TP") (pinfunction "TP_TP") (pintype "input"))
    )
    (net (code "2") (name "FL_CS") (class "Default")
      (node (ref "IC4") (pin "23") (pinfunction "PTC2_23") (pintype "bidirectional"))
      (node (ref "IC6") (pin "1") (pinfunction "~{CE/CS}_1") (pintype "bidirectional"))
    )
    (net (code "3") (name "FL_RESET") (class "Default")
      (node (ref "IC4") (pin "20") (pinfunction "PTB0/LLWU_P5_20") (pintype "bidirectional"))
      (node (ref "IC6") (pin "7") (pinfunction "~{RESET}_7") (pintype "bidirectional"))
    )
    (net (code "4") (name "FL_W") (class "Default")
      (node (ref "IC4") (pin "22") (pinfunction "PTC1/LLWU_P6/RTC_CLKIN_22") (pintype "bidirectional"))
      (node (ref "IC6") (pin "3") (pinfunction "~{WP}_3") (pintype "bidirectional"))
    )
    (net (code "5") (name "GND") (class "Default")
      (node (ref "BAT") (pin "2") (pinfunction "1_2") (pintype "passive"))
      (node (ref "C1") (pin "2") (pinfunction "2_2") (pintype "passive"))
      (node (ref "C10") (pin "2") (pinfunction "2_2") (pintype "passive"))
      (node (ref "C11") (pin "2") (pinfunction "2_2") (pintype "passive"))
      (node (ref "C12") (pin "2") (pinfunction "2_2") (pintype "passive"))
      (node (ref "C13") (pin "2") (pinfunction "2_2") (pintype "passive"))
      (node (ref "C14") (pin "2") (pinfunction "2_2") (pintype "passive"))
      (node (ref "C15") (pin "2") (pinfunction "2_2") (pintype "passive"))
      (node (ref "C16") (pin "2") (pinfunction "2_2") (pintype "passive"))
      (node (ref "C17") (pin "2") (pinfunction "2_2") (pintype "passive"))
      (node (ref "C18") (pin "2") (pinfunction "2_2") (pintype "passive"))
      (node (ref "C19") (pin "2") (pinfunction "2_2") (pintype "passive"))
      (node (ref "C2") (pin "2") (pinfunction "2_2") (pintype "passive"))
      (node (ref "C20") (pin "2") (pinfunction "2_2") (pintype "passive"))
      (node (ref "C21") (pin "2") (pinfunction "2_2") (pintype "passive"))
      (node (ref "C22") (pin "2") (pinfunction "2_2") (pintype "passive"))
      (node (ref "C23") (pin "2") (pinfunction "2_2") (pintype "passive"))
      (node (ref "C24") (pin "2") (pinfunction "2_2") (pintype "passive"))
      (node (ref "C25") (pin "2") (pinfunction "2_2") (pintype "passive"))
      (node (ref "C26") (pin "2") (pinfunction "2_2") (pintype "passive"))
      (node (ref "C27") (pin "2") (pinfunction "2_2") (pintype "passive"))
      (node (ref "C28") (pin "2") (pinfunction "2_2") (pintype "passive"))
      (node (ref "C29") (pin "2") (pinfunction "2_2") (pintype "passive"))
      (node (ref "C3") (pin "-") (pinfunction "-_-") (pintype "passive"))
      (node (ref "C30") (pin "2") (pinfunction "2_2") (pintype "passive"))
      (node (ref "C31") (pin "2") (pinfunction "2_2") (pintype "passive"))
      (node (ref "C33") (pin "2") (pinfunction "2_2") (pintype "passive"))
      (node (ref "C34") (pin "2") (pinfunction "2_2") (pintype "passive"))
      (node (ref "C35") (pin "2") (pinfunction "2_2") (pintype "passive"))
      (node (ref "C36") (pin "2") (pinfunction "2_2") (pintype "passive"))
      (node (ref "C37") (pin "2") (pinfunction "2_2") (pintype "passive"))
      (node (ref "C38") (pin "2") (pinfunction "2_2") (pintype "passive"))
      (node (ref "C39") (pin "2") (pinfunction "2_2") (pintype "passive"))
      (node (ref "C4") (pin "2") (pinfunction "2_2") (pintype "passive"))
      (node (ref "C40") (pin "2") (pinfunction "2_2") (pintype "passive"))
      (node (ref "C41") (pin "2") (pinfunction "2_2") (pintype "passive"))
      (node (ref "C42") (pin "2") (pinfunction "2_2") (pintype "passive"))
      (node (ref "C5") (pin "2") (pinfunction "2_2") (pintype "passive"))
      (node (ref "C7") (pin "2") (pinfunction "2_2") (pintype "passive"))
      (node (ref "C8") (pin "2") (pinfunction "2_2") (pintype "passive"))
      (node (ref "C9") (pin "2") (pinfunction "2_2") (pintype "passive"))
      (node (ref "D1") (pin "2") (pinfunction "2_2") (pintype "bidirectional"))
      (node (ref "D4") (pin "A") (pinfunction "A_A") (pintype "passive"))
      (node (ref "EXP1") (pin "1") (pinfunction "S_1") (pintype "passive"))
      (node (ref "EXP1") (pin "13") (pinfunction "S_13") (pintype "passive"))
      (node (ref "EXP1") (pin "14") (pinfunction "S_14") (pintype "passive"))
      (node (ref "EXP1") (pin "26") (pinfunction "S_26") (pintype "passive"))
      (node (ref "I2C") (pin "4") (pinfunction "4_4") (pintype "bidirectional"))
      (node (ref "IC1") (pin "13") (pinfunction "VSS_13") (pintype "bidirectional"))
      (node (ref "IC1") (pin "33") (pinfunction "VSS_2_33") (pintype "bidirectional"))
      (node (ref "IC1") (pin "34") (pinfunction "VSS_3_34") (pintype "bidirectional"))
      (node (ref "IC1") (pin "GND") (pinfunction "DIE_PAD_GND") (pintype "bidirectional"))
      (node (ref "IC3") (pin "4") (pinfunction "GND_4") (pintype "bidirectional"))
      (node (ref "IC3") (pin "EP") (pinfunction "EP_EP") (pintype "bidirectional"))
      (node (ref "IC4") (pin "16") (pinfunction "VSS_2_16") (pintype "power_in"))
      (node (ref "IC4") (pin "2") (pinfunction "VSS_2") (pintype "power_in"))
      (node (ref "IC4") (pin "33") (pinfunction "EPAD_33") (pintype "passive"))
      (node (ref "IC4") (pin "8") (pinfunction "VSSA_8") (pintype "power_in"))
      (node (ref "IC5") (pin "2") (pinfunction "V-_2") (pintype "power_in"))
      (node (ref "IC6") (pin "4") (pinfunction "GND_4") (pintype "bidirectional"))
      (node (ref "IC6") (pin "EP") (pinfunction "GND_EP") (pintype "bidirectional"))
      (node (ref "JP1") (pin "1") (pinfunction "1_1") (pintype "passive"))
      (node (ref "JP1") (pin "4") (pinfunction "4_4") (pintype "passive"))
      (node (ref "JP1") (pin "6") (pinfunction "6_6") (pintype "passive"))
      (node (ref "LED1") (pin "4") (pinfunction "GND_4") (pintype "power_in"))
      (node (ref "MIC1") (pin "2") (pinfunction "GND_2") (pintype "bidirectional"))
      (node (ref "MIC1") (pin "3") (pinfunction "GND_3") (pintype "bidirectional"))
      (node (ref "P_GND") (pin "1") (pinfunction "1_1") (pintype "bidirectional"))
      (node (ref "Q2") (pin "2") (pinfunction "G2_2") (pintype "power_in"))
      (node (ref "Q2") (pin "4") (pinfunction "G1_4") (pintype "power_in"))
      (node (ref "Q3") (pin "2") (pinfunction "G2_2") (pintype "power_in"))
      (node (ref "Q3") (pin "4") (pinfunction "G1_4") (pintype "power_in"))
      (node (ref "R21") (pin "1") (pinfunction "1_1") (pintype "passive"))
      (node (ref "R35") (pin "1") (pinfunction "1_1") (pintype "passive"))
      (node (ref "R43") (pin "1") (pinfunction "1_1") (pintype "passive"))
      (node (ref "R5") (pin "1") (pinfunction "1_1") (pintype "passive"))
      (node (ref "SERIAL") (pin "4") (pinfunction "4_4") (pintype "bidirectional"))
      (node (ref "TAST_A") (pin "1") (pinfunction "P1_1") (pintype "passive"))
      (node (ref "TAST_A") (pin "2") (pinfunction "P2_2") (pintype "passive"))
      (node (ref "TAST_B") (pin "1") (pinfunction "P1_1") (pintype "passive"))
      (node (ref "TAST_B") (pin "2") (pinfunction "P2_2") (pintype "passive"))
      (node (ref "TAST_RESET") (pin "1") (pinfunction "P_1") (pintype "passive"))
      (node (ref "TAST_RESET") (pin "2") (pinfunction "P1_2") (pintype "passive"))
      (node (ref "TP11") (pin "TP") (pinfunction "TP_TP") (pintype "input"))
      (node (ref "TP16") (pin "TP") (pinfunction "TP_TP") (pintype "input"))
      (node (ref "U$2") (pin "GND") (pinfunction "GND_GND") (pintype "bidirectional"))
      (node (ref "U$2") (pin "GND@1") (pinfunction "GND_GND@1") (pintype "bidirectional"))
      (node (ref "U1") (pin "12") (pinfunction "SDO2_12") (pintype "bidirectional"))
      (node (ref "U1") (pin "17") (pinfunction "SDO1_17") (pintype "bidirectional"))
      (node (ref "U1") (pin "20") (pinfunction "CSB3_20") (pintype "bidirectional"))
      (node (ref "U1") (pin "4") (pinfunction "GNDA_4") (pintype "bidirectional"))
      (node (ref "U1") (pin "6") (pinfunction "GNDIO_6") (pintype "bidirectional"))
      (node (ref "USB2") (pin "5") (pinfunction "5_5") (pintype "bidirectional"))
      (node (ref "USB2") (pin "P$1") (pinfunction "5_P$1") (pintype "bidirectional"))
      (node (ref "USB2") (pin "P$2") (pinfunction "5_P$2") (pintype "bidirectional"))
      (node (ref "USB2") (pin "P$3") (pinfunction "5_P$3") (pintype "bidirectional"))
      (node (ref "USB2") (pin "P$4") (pinfunction "5_P$4") (pintype "bidirectional"))
    )
    (net (code "6") (name "LED_C1") (class "Default")
      (node (ref "LED12") (pin "A") (pinfunction "A_A") (pintype "passive"))
      (node (ref "LED21") (pin "A") (pinfunction "A_A") (pintype "passive"))
      (node (ref "LED3") (pin "A") (pinfunction "A_A") (pintype "passive"))
      (node (ref "R1") (pin "2") (pinfunction "2_2") (pintype "passive"))
    )
    (net (code "7") (name "LED_C2") (class "Default")
      (node (ref "LED13") (pin "A") (pinfunction "A_A") (pintype "passive"))
      (node (ref "LED22") (pin "A") (pinfunction "A_A") (pintype "passive"))
      (node (ref "LED4") (pin "A") (pinfunction "A_A") (pintype "passive"))
      (node (ref "R8") (pin "2") (pinfunction "2_2") (pintype "passive"))
    )
    (net (code "8") (name "LED_C3") (class "Default")
      (node (ref "LED14") (pin "A") (pinfunction "A_A") (pintype "passive"))
      (node (ref "LED23") (pin "A") (pinfunction "A_A") (pintype "passive"))
      (node (ref "LED5") (pin "A") (pinfunction "A_A") (pintype "passive"))
      (node (ref "R9") (pin "2") (pinfunction "2_2") (pintype "passive"))
    )
    (net (code "9") (name "LED_C4") (class "Default")
      (node (ref "LED15") (pin "A") (pinfunction "A_A") (pintype "passive"))
      (node (ref "LED24") (pin "A") (pinfunction "A_A") (pintype "passive"))
      (node (ref "LED6") (pin "A") (pinfunction "A_A") (pintype "passive"))
      (node (ref "R10") (pin "2") (pinfunction "2_2") (pintype "passive"))
    )
    (net (code "10") (name "LED_C5") (class "Default")
      (node (ref "LED16") (pin "A") (pinfunction "A_A") (pintype "passive"))
      (node (ref "LED25") (pin "A") (pinfunction "A_A") (pintype "passive"))
      (node (ref "LED7") (pin "A") (pinfunction "A_A") (pintype "passive"))
      (node (ref "R11") (pin "2") (pinfunction "2_2") (pintype "passive"))
    )
    (net (code "11") (name "LED_C6") (class "Default")
      (node (ref "LED17") (pin "A") (pinfunction "A_A") (pintype "passive"))
      (node (ref "LED26") (pin "A") (pinfunction "A_A") (pintype "passive"))
      (node (ref "LED8") (pin "A") (pinfunction "A_A") (pintype "passive"))
      (node (ref "R12") (pin "2") (pinfunction "2_2") (pintype "passive"))
    )
    (net (code "12") (name "LED_C7") (class "Default")
      (node (ref "LED18") (pin "A") (pinfunction "A_A") (pintype "passive"))
      (node (ref "LED27") (pin "A") (pinfunction "A_A") (pintype "passive"))
      (node (ref "LED9") (pin "A") (pinfunction "A_A") (pintype "passive"))
      (node (ref "R13") (pin "2") (pinfunction "2_2") (pintype "passive"))
    )
    (net (code "13") (name "LED_C8") (class "Default")
      (node (ref "LED10") (pin "A") (pinfunction "A_A") (pintype "passive"))
      (node (ref "LED28") (pin "A") (pinfunction "A_A") (pintype "passive"))
      (node (ref "R14") (pin "2") (pinfunction "2_2") (pintype "passive"))
    )
    (net (code "14") (name "LED_C9") (class "Default")
      (node (ref "LED11") (pin "A") (pinfunction "A_A") (pintype "passive"))
      (node (ref "LED29") (pin "A") (pinfunction "A_A") (pintype "passive"))
      (node (ref "R15") (pin "2") (pinfunction "2_2") (pintype "passive"))
    )
    (net (code "15") (name "LED_R1") (class "Default")
      (node (ref "LED10") (pin "C") (pinfunction "C_C") (pintype "passive"))
      (node (ref "LED11") (pin "C") (pinfunction "C_C") (pintype "passive"))
      (node (ref "LED3") (pin "C") (pinfunction "C_C") (pintype "passive"))
      (node (ref "LED4") (pin "C") (pinfunction "C_C") (pintype "passive"))
      (node (ref "LED5") (pin "C") (pinfunction "C_C") (pintype "passive"))
      (node (ref "LED6") (pin "C") (pinfunction "C_C") (pintype "passive"))
      (node (ref "LED7") (pin "C") (pinfunction "C_C") (pintype "passive"))
      (node (ref "LED8") (pin "C") (pinfunction "C_C") (pintype "passive"))
      (node (ref "LED9") (pin "C") (pinfunction "C_C") (pintype "passive"))
      (node (ref "R16") (pin "2") (pinfunction "2_2") (pintype "passive"))
    )
    (net (code "16") (name "LED_R2") (class "Default")
      (node (ref "LED12") (pin "C") (pinfunction "C_C") (pintype "passive"))
      (node (ref "LED13") (pin "C") (pinfunction "C_C") (pintype "passive"))
      (node (ref "LED14") (pin "C") (pinfunction "C_C") (pintype "passive"))
      (node (ref "LED15") (pin "C") (pinfunction "C_C") (pintype "passive"))
      (node (ref "LED16") (pin "C") (pinfunction "C_C") (pintype "passive"))
      (node (ref "LED17") (pin "C") (pinfunction "C_C") (pintype "passive"))
      (node (ref "LED18") (pin "C") (pinfunction "C_C") (pintype "passive"))
      (node (ref "R17") (pin "2") (pinfunction "2_2") (pintype "passive"))
    )
    (net (code "17") (name "LED_R3") (class "Default")
      (node (ref "LED21") (pin "C") (pinfunction "C_C") (pintype "passive"))
      (node (ref "LED22") (pin "C") (pinfunction "C_C") (pintype "passive"))
      (node (ref "LED23") (pin "C") (pinfunction "C_C") (pintype "passive"))
      (node (ref "LED24") (pin "C") (pinfunction "C_C") (pintype "passive"))
      (node (ref "LED25") (pin "C") (pinfunction "C_C") (pintype "passive"))
      (node (ref "LED26") (pin "C") (pinfunction "C_C") (pintype "passive"))
      (node (ref "LED27") (pin "C") (pinfunction "C_C") (pintype "passive"))
      (node (ref "LED28") (pin "C") (pinfunction "C_C") (pintype "passive"))
      (node (ref "LED29") (pin "C") (pinfunction "C_C") (pintype "passive"))
      (node (ref "R18") (pin "2") (pinfunction "2_2") (pintype "passive"))
    )
    (net (code "18") (name "MISO") (class "Default")
      (node (ref "IC4") (pin "32") (pinfunction "PTD7_32") (pintype "bidirectional"))
      (node (ref "R44") (pin "2") (pinfunction "2_2") (pintype "passive"))
      (node (ref "R45") (pin "1") (pinfunction "1_1") (pintype "passive"))
    )
    (net (code "19") (name "MISO_FL") (class "Default")
      (node (ref "IC4") (pin "28") (pinfunction "PTC7_28") (pintype "bidirectional"))
      (node (ref "IC6") (pin "2") (pinfunction "SO/MISO_2") (pintype "bidirectional"))
      (node (ref "R45") (pin "2") (pinfunction "2_2") (pintype "passive"))
    )
    (net (code "20") (name "MOSI") (class "Default")
      (node (ref "IC4") (pin "31") (pinfunction "PTD6/LLWU_P15_31") (pintype "bidirectional"))
      (node (ref "IC6") (pin "5") (pinfunction "SI/MOSI_5") (pintype "bidirectional"))
    )
    (net (code "21") (name "Net-(BAT-2)") (class "Default")
      (node (ref "BAT") (pin "1") (pinfunction "2_1") (pintype "passive"))
      (node (ref "Q1") (pin "3") (pinfunction "D_3") (pintype "passive"))
      (node (ref "TP10") (pin "TP") (pinfunction "TP_TP") (pintype "input"))
    )
    (net (code "22") (name "Net-(C12-Pad1)") (class "Default")
      (node (ref "C12") (pin "1") (pinfunction "1_1") (pintype "passive"))
      (node (ref "C6") (pin "2") (pinfunction "2_2") (pintype "passive"))
      (node (ref "L5") (pin "1") (pinfunction "1_1") (pintype "passive"))
    )
    (net (code "23") (name "Net-(C13-Pad1)") (class "Default")
      (node (ref "C13") (pin "1") (pinfunction "1_1") (pintype "passive"))
      (node (ref "L5") (pin "2") (pinfunction "2_2") (pintype "passive"))
      (node (ref "U$2") (pin "FEED") (pinfunction "FEED_FEED") (pintype "bidirectional"))
    )
    (net (code "24") (name "Net-(C32-Pad1)") (class "Default")
      (node (ref "C32") (pin "1") (pinfunction "1_1") (pintype "passive"))
      (node (ref "R40") (pin "2") (pinfunction "2_2") (pintype "passive"))
    )
    (net (code "25") (name "Net-(D1-Pad1)") (class "Default")
      (node (ref "D1") (pin "1") (pinfunction "1_1") (pintype "bidirectional"))
      (node (ref "D1") (pin "6") (pinfunction "6_6") (pintype "bidirectional"))
      (node (ref "L1") (pin "1") (pinfunction "1_1") (pintype "passive"))
      (node (ref "TP13") (pin "TP") (pinfunction "TP_TP") (pintype "input"))
      (node (ref "USB2") (pin "3") (pinfunction "3_3") (pintype "bidirectional"))
    )
    (net (code "26") (name "Net-(F1-Pad2)") (class "Default")
      (node (ref "F1") (pin "2") (pinfunction "2_2") (pintype "passive"))
      (node (ref "P_+3V") (pin "1") (pinfunction "1_1") (pintype "bidirectional"))
    )
    (net (code "27") (name "Net-(IC1-ANT1)") (class "Default")
      (node (ref "IC1") (pin "31") (pinfunction "ANT1_31") (pintype "bidirectional"))
      (node (ref "L4") (pin "2") (pinfunction "2_2") (pintype "passive"))
      (node (ref "L6") (pin "2") (pinfunction "2_2") (pintype "passive"))
    )
    (net (code "28") (name "Net-(IC1-ANT2)") (class "Default")
      (node (ref "C6") (pin "1") (pinfunction "1_1") (pintype "passive"))
      (node (ref "IC1") (pin "32") (pinfunction "ANT2_32") (pintype "bidirectional"))
      (node (ref "L4") (pin "1") (pinfunction "1_1") (pintype "passive"))
    )
    (net (code "29") (name "Net-(IC1-DEC1)") (class "Default")
      (node (ref "C19") (pin "1") (pinfunction "1_1") (pintype "passive"))
      (node (ref "IC1") (pin "39") (pinfunction "DEC1_39") (pintype "bidirectional"))
    )
    (net (code "30") (name "Net-(IC1-DEC2)") (class "Default")
      (node (ref "C10") (pin "1") (pinfunction "1_1") (pintype "passive"))
      (node (ref "IC1") (pin "29") (pinfunction "DEC2_29") (pintype "bidirectional"))
    )
    (net (code "31") (name "Net-(IC1-VDD_PA)") (class "Default")
      (node (ref "C14") (pin "1") (pinfunction "1_1") (pintype "passive"))
      (node (ref "IC1") (pin "30") (pinfunction "VDD_PA_30") (pintype "bidirectional"))
      (node (ref "L6") (pin "1") (pinfunction "1_1") (pintype "passive"))
    )
    (net (code "32") (name "Net-(IC1-XC1)") (class "Default")
      (node (ref "C23") (pin "1") (pinfunction "1_1") (pintype "passive"))
      (node (ref "IC1") (pin "37") (pinfunction "XC1_37") (pintype "bidirectional"))
      (node (ref "Q2") (pin "1") (pinfunction "X1_1") (pintype "bidirectional"))
    )
    (net (code "33") (name "Net-(IC1-XC2)") (class "Default")
      (node (ref "C25") (pin "1") (pinfunction "1_1") (pintype "passive"))
      (node (ref "IC1") (pin "38") (pinfunction "XC2_38") (pintype "bidirectional"))
      (node (ref "Q2") (pin "3") (pinfunction "X2_3") (pintype "bidirectional"))
    )
    (net (code "34") (name "Net-(IC3-OUT1)") (class "Default")
      (node (ref "IC3") (pin "2") (pinfunction "OUT1_2") (pintype "bidirectional"))
      (node (ref "JP1") (pin "3") (pinfunction "3_3") (pintype "passive"))
      (node (ref "R4") (pin "1") (pinfunction "1_1") (pintype "passive"))
    )
    (net (code "35") (name "Net-(IC3-OUT2)") (class "Default")
      (node (ref "IC3") (pin "3") (pinfunction "OUT2_3") (pintype "bidirectional"))
      (node (ref "JP1") (pin "2") (pinfunction "2_2") (pintype "passive"))
      (node (ref "SPK1") (pin "1") (pinfunction "1_1") (pintype "bidirectional"))
    )
    (net (code "36") (name "Net-(IC4-PTA0)") (class "Default")
      (node (ref "IC4") (pin "10") (pinfunction "PTA0_10") (pintype "bidirectional"))
      (node (ref "TP1") (pin "TP") (pinfunction "TP_TP") (pintype "input"))
    )
    (net (code "37") (name "Net-(IC4-PTA3)") (class "Default")
      (node (ref "IC4") (pin "13") (pinfunction "PTA3_13") (pintype "bidirectional"))
      (node (ref "TP4") (pin "TP") (pinfunction "TP_TP") (pintype "input"))
    )
    (net (code "38") (name "Net-(IC4-PTA4)") (class "Default")
      (node (ref "IC4") (pin "14") (pinfunction "PTA4_14") (pintype "bidirectional"))
      (node (ref "R33") (pin "1") (pinfunction "1_1") (pintype "passive"))
    )
    (net (code "39") (name "Net-(IC4-PTA18)") (class "Default")
      (node (ref "C21") (pin "1") (pinfunction "1_1") (pintype "passive"))
      (node (ref "IC4") (pin "17") (pinfunction "PTA18_17") (pintype "bidirectional"))
      (node (ref "Q3") (pin "1") (pinfunction "X1_1") (pintype "bidirectional"))
    )
    (net (code "40") (name "Net-(IC4-PTA19)") (class "Default")
      (node (ref "C22") (pin "1") (pinfunction "1_1") (pintype "passive"))
      (node (ref "IC4") (pin "18") (pinfunction "PTA19_18") (pintype "bidirectional"))
      (node (ref "Q3") (pin "3") (pinfunction "X2_3") (pintype "bidirectional"))
    )
    (net (code "41") (name "Net-(IC4-PTA20)") (class "Default")
      (node (ref "C11") (pin "1") (pinfunction "1_1") (pintype "passive"))
      (node (ref "IC4") (pin "19") (pinfunction "PTA20_19") (pintype "bidirectional"))
      (node (ref "R35") (pin "2") (pinfunction "2_2") (pintype "passive"))
      (node (ref "R36") (pin "1") (pinfunction "1_1") (pintype "passive"))
      (node (ref "R44") (pin "1") (pinfunction "1_1") (pintype "passive"))
    )
    (net (code "42") (name "Net-(IC4-PTD4{slash}LLWU_P14)") (class "Default")
      (node (ref "IC4") (pin "29") (pinfunction "PTD4/LLWU_P14_29") (pintype "bidirectional"))
      (node (ref "LED2") (pin "A") (pinfunction "A_A") (pintype "passive"))
    )
    (net (code "43") (name "Net-(IC5A-+IN)") (class "Default")
      (node (ref "C33") (pin "1") (pinfunction "1_1") (pintype "passive"))
      (node (ref "IC5") (pin "3") (pinfunction "+IN_3") (pintype "input"))
      (node (ref "R42") (pin "1") (pinfunction "1_1") (pintype "passive"))
      (node (ref "R43") (pin "2") (pinfunction "2_2") (pintype "passive"))
    )
    (net (code "44") (name "Net-(IC5A--IN)") (class "Default")
      (node (ref "IC5") (pin "4") (pinfunction "-IN_4") (pintype "input"))
      (node (ref "R40") (pin "1") (pinfunction "1_1") (pintype "passive"))
      (node (ref "R41") (pin "2") (pinfunction "2_2") (pintype "passive"))
    )
    (net (code "45") (name "Net-(L1-2)") (class "Default")
      (node (ref "D1") (pin "3") (pinfunction "3_3") (pintype "bidirectional"))
      (node (ref "D1") (pin "4") (pinfunction "4_4") (pintype "bidirectional"))
      (node (ref "L1") (pin "4") (pinfunction "2_4") (pintype "passive"))
      (node (ref "TP14") (pin "TP") (pinfunction "TP_TP") (pintype "input"))
      (node (ref "USB2") (pin "2") (pinfunction "2_2") (pintype "bidirectional"))
    )
    (net (code "46") (name "Net-(L1-3)") (class "Default")
      (node (ref "L1") (pin "2") (pinfunction "3_2") (pintype "passive"))
      (node (ref "R47") (pin "1") (pinfunction "1_1") (pintype "passive"))
    )
    (net (code "47") (name "Net-(L1-4)") (class "Default")
      (node (ref "L1") (pin "3") (pinfunction "4_3") (pintype "passive"))
      (node (ref "R46") (pin "1") (pinfunction "1_1") (pintype "passive"))
    )
    (net (code "48") (name "Net-(L2-Pad1)") (class "Default")
      (node (ref "L2") (pin "1") (pinfunction "1_1") (pintype "passive"))
      (node (ref "USB2") (pin "1") (pinfunction "1_1") (pintype "bidirectional"))
    )
    (net (code "49") (name "Net-(LED2-PadC)") (class "Default")
      (node (ref "LED2") (pin "C") (pinfunction "C_C") (pintype "passive"))
      (node (ref "R34") (pin "1") (pinfunction "1_1") (pintype "passive"))
    )
    (net (code "50") (name "Net-(MIC1-OUT)") (class "Default")
      (node (ref "C32") (pin "2") (pinfunction "2_2") (pintype "passive"))
      (node (ref "MIC1") (pin "4") (pinfunction "OUT_4") (pintype "bidirectional"))
    )
    (net (code "51") (name "Net-(Q1-G)") (class "Default")
      (node (ref "Q1") (pin "1") (pinfunction "G_1") (pintype "passive"))
      (node (ref "R49") (pin "2") (pinfunction "2_2") (pintype "passive"))
      (node (ref "R5") (pin "2") (pinfunction "2_2") (pintype "passive"))
    )
    (net (code "52") (name "Net-(Q4-G)") (class "Default")
      (node (ref "Q4") (pin "1") (pinfunction "G_1") (pintype "passive"))
      (node (ref "R21") (pin "2") (pinfunction "2_2") (pintype "passive"))
    )
    (net (code "53") (name "Net-(R4-Pad2)") (class "Default")
      (node (ref "R4") (pin "2") (pinfunction "2_2") (pintype "passive"))
      (node (ref "SPK1") (pin "2") (pinfunction "2_2") (pintype "bidirectional"))
    )
    (net (code "54") (name "Net-(U1-DRDYM)") (class "Default")
      (node (ref "R31") (pin "1") (pinfunction "1_1") (pintype "passive"))
      (node (ref "U1") (pin "2") (pinfunction "DRDYM_2") (pintype "bidirectional"))
    )
    (net (code "55") (name "Net-(U1-INT1)") (class "Default")
      (node (ref "R29") (pin "2") (pinfunction "2_2") (pintype "passive"))
      (node (ref "U1") (pin "19") (pinfunction "INT1_19") (pintype "bidirectional"))
    )
    (net (code "56") (name "Net-(U1-INT3)") (class "Default")
      (node (ref "R32") (pin "2") (pinfunction "2_2") (pintype "passive"))
      (node (ref "U1") (pin "14") (pinfunction "INT3_14") (pintype "bidirectional"))
    )
    (net (code "57") (name "P0") (class "Default")
      (node (ref "EXP1") (pin "24") (pinfunction "S_24") (pintype "passive"))
      (node (ref "IC1") (pin "4") (pinfunction "P0.00_4") (pintype "bidirectional"))
      (node (ref "P_0") (pin "1") (pinfunction "1_1") (pintype "bidirectional"))
      (node (ref "R6") (pin "1") (pinfunction "1_1") (pintype "passive"))
    )
    (net (code "58") (name "P1") (class "Default")
      (node (ref "EXP1") (pin "23") (pinfunction "S_23") (pintype "passive"))
      (node (ref "IC1") (pin "5") (pinfunction "P0.01_5") (pintype "bidirectional"))
      (node (ref "P_1") (pin "1") (pinfunction "1_1") (pintype "bidirectional"))
      (node (ref "R7") (pin "1") (pinfunction "1_1") (pintype "passive"))
    )
    (net (code "59") (name "P2") (class "Default")
      (node (ref "EXP1") (pin "22") (pinfunction "S_22") (pintype "passive"))
      (node (ref "IC1") (pin "6") (pinfunction "P0.02_6") (pintype "bidirectional"))
      (node (ref "P_2") (pin "1") (pinfunction "1_1") (pintype "bidirectional"))
      (node (ref "R19") (pin "1") (pinfunction "1_1") (pintype "passive"))
    )
    (net (code "60") (name "P3") (class "Default")
      (node (ref "C34") (pin "1") (pinfunction "1_1") (pintype "passive"))
      (node (ref "IC1") (pin "7") (pinfunction "P0.03_7") (pintype "bidirectional"))
      (node (ref "IC5") (pin "1") (pinfunction "OUT_1") (pintype "output"))
      (node (ref "R41") (pin "1") (pinfunction "1_1") (pintype "passive"))
    )
    (net (code "61") (name "P4") (class "Default")
      (node (ref "EXP1") (pin "20") (pinfunction "S_20") (pintype "passive"))
      (node (ref "IC1") (pin "8") (pinfunction "P0.04_8") (pintype "bidirectional"))
      (node (ref "R1") (pin "1") (pinfunction "1_1") (pintype "passive"))
    )
    (net (code "62") (name "P5") (class "Default")
      (node (ref "EXP1") (pin "19") (pinfunction "S_19") (pintype "passive"))
      (node (ref "IC1") (pin "9") (pinfunction "P0.05_9") (pintype "bidirectional"))
      (node (ref "R8") (pin "1") (pinfunction "1_1") (pintype "passive"))
    )
    (net (code "63") (name "P6") (class "Default")
      (node (ref "EXP1") (pin "18") (pinfunction "S_18") (pintype "passive"))
      (node (ref "IC1") (pin "10") (pinfunction "P0.06_10") (pintype "bidirectional"))
      (node (ref "R9") (pin "1") (pinfunction "1_1") (pintype "passive"))
    )
    (net (code "64") (name "P7") (class "Default")
      (node (ref "EXP1") (pin "17") (pinfunction "S_17") (pintype "passive"))
      (node (ref "IC1") (pin "11") (pinfunction "P0.07_11") (pintype "bidirectional"))
      (node (ref "R10") (pin "1") (pinfunction "1_1") (pintype "passive"))
    )
    (net (code "65") (name "P8") (class "Default")
      (node (ref "EXP1") (pin "16") (pinfunction "S_16") (pintype "passive"))
      (node (ref "IC1") (pin "14") (pinfunction "P0.08_14") (pintype "bidirectional"))
      (node (ref "R11") (pin "1") (pinfunction "1_1") (pintype "passive"))
    )
    (net (code "66") (name "P9") (class "Default")
      (node (ref "EXP1") (pin "15") (pinfunction "S_15") (pintype "passive"))
      (node (ref "IC1") (pin "15") (pinfunction "P0.09_15") (pintype "bidirectional"))
      (node (ref "R12") (pin "1") (pinfunction "1_1") (pintype "passive"))
    )
    (net (code "67") (name "P10") (class "Default")
      (node (ref "EXP1") (pin "12") (pinfunction "S_12") (pintype "passive"))
      (node (ref "IC1") (pin "16") (pinfunction "P0.10_16") (pintype "bidirectional"))
      (node (ref "R13") (pin "1") (pinfunction "1_1") (pintype "passive"))
    )
    (net (code "68") (name "P11") (class "Default")
      (node (ref "EXP1") (pin "11") (pinfunction "S_11") (pintype "passive"))
      (node (ref "IC1") (pin "17") (pinfunction "P0.11_17") (pintype "bidirectional"))
      (node (ref "R14") (pin "1") (pinfunction "1_1") (pintype "passive"))
    )
    (net (code "69") (name "P12") (class "Default")
      (node (ref "EXP1") (pin "10") (pinfunction "S_10") (pintype "passive"))
      (node (ref "IC1") (pin "18") (pinfunction "P0.12_18") (pintype "bidirectional"))
      (node (ref "R15") (pin "1") (pinfunction "1_1") (pintype "passive"))
    )
    (net (code "70") (name "P13") (class "Default")
      (node (ref "EXP1") (pin "9") (pinfunction "S_9") (pintype "passive"))
      (node (ref "IC1") (pin "19") (pinfunction "P0.13_19") (pintype "bidirectional"))
      (node (ref "R16") (pin "1") (pinfunction "1_1") (pintype "passive"))
    )
    (net (code "71") (name "P14") (class "Default")
      (node (ref "EXP1") (pin "8") (pinfunction "S_8") (pintype "passive"))
      (node (ref "IC1") (pin "20") (pinfunction "P0.14_20") (pintype "bidirectional"))
      (node (ref "R17") (pin "1") (pinfunction "1_1") (pintype "passive"))
    )
    (net (code "72") (name "P15") (class "Default")
      (node (ref "EXP1") (pin "7") (pinfunction "S_7") (pintype "passive"))
      (node (ref "IC1") (pin "21") (pinfunction "P0.15_21") (pintype "bidirectional"))
      (node (ref "R18") (pin "1") (pinfunction "1_1") (pintype "passive"))
    )
    (net (code "73") (name "P16") (class "Default")
      (node (ref "IC1") (pin "22") (pinfunction "P0.16_22") (pintype "bidirectional"))
      (node (ref "R2") (pin "1") (pinfunction "1_1") (pintype "passive"))
      (node (ref "TAST_B") (pin "3") (pinfunction "S1_3") (pintype "passive"))
      (node (ref "TAST_B") (pin "4") (pinfunction "S2_4") (pintype "passive"))
    )
    (net (code "74") (name "P17") (class "Default")
      (node (ref "IC1") (pin "25") (pinfunction "P0.17_25") (pintype "bidirectional"))
      (node (ref "R3") (pin "1") (pinfunction "1_1") (pintype "passive"))
      (node (ref "TAST_A") (pin "3") (pinfunction "S1_3") (pintype "passive"))
      (node (ref "TAST_A") (pin "4") (pinfunction "S2_4") (pintype "passive"))
    )
    (net (code "75") (name "P18") (class "Default")
      (node (ref "IC1") (pin "26") (pinfunction "P0.18_26") (pintype "bidirectional"))
      (node (ref "LED1") (pin "1") (pinfunction "DI_1") (pintype "input"))
    )
    (net (code "76") (name "P19") (class "Default")
      (node (ref "IC1") (pin "27") (pinfunction "P0.19_27") (pintype "bidirectional"))
      (node (ref "R24") (pin "1") (pinfunction "1_1") (pintype "passive"))
    )
    (net (code "77") (name "P20") (class "Default")
      (node (ref "IC1") (pin "28") (pinfunction "P0.20_28") (pintype "bidirectional"))
      (node (ref "R23") (pin "1") (pinfunction "1_1") (pintype "passive"))
    )
    (net (code "78") (name "P21") (class "Default")
      (node (ref "IC1") (pin "40") (pinfunction "P0.21_40") (pintype "bidirectional"))
      (node (ref "R29") (pin "1") (pinfunction "1_1") (pintype "passive"))
      (node (ref "R30") (pin "1") (pinfunction "1_1") (pintype "passive"))
      (node (ref "R32") (pin "1") (pinfunction "1_1") (pintype "passive"))
    )
    (net (code "79") (name "P22") (class "Default")
      (node (ref "EXP1") (pin "21") (pinfunction "S_21") (pintype "passive"))
      (node (ref "IC1") (pin "41") (pinfunction "P0.22_41") (pintype "bidirectional"))
      (node (ref "P_3") (pin "1") (pinfunction "1_1") (pintype "bidirectional"))
      (node (ref "R20") (pin "1") (pinfunction "1_1") (pintype "passive"))
    )
    (net (code "80") (name "P23") (class "Default")
      (node (ref "IC1") (pin "42") (pinfunction "P0.23_42") (pintype "bidirectional"))
      (node (ref "R31") (pin "2") (pinfunction "2_2") (pintype "passive"))
      (node (ref "R48") (pin "1") (pinfunction "1_1") (pintype "passive"))
    )
    (net (code "81") (name "P24") (class "Default")
      (node (ref "IC1") (pin "43") (pinfunction "P0.24_43") (pintype "bidirectional"))
      (node (ref "R39") (pin "2") (pinfunction "2_2") (pintype "passive"))
    )
    (net (code "82") (name "P25") (class "Default")
      (node (ref "IC1") (pin "44") (pinfunction "P0.25_44") (pintype "bidirectional"))
      (node (ref "R38") (pin "2") (pinfunction "2_2") (pintype "passive"))
    )
    (net (code "83") (name "P26") (class "Default")
      (node (ref "C42") (pin "1") (pinfunction "1_1") (pintype "passive"))
      (node (ref "EXP1") (pin "6") (pinfunction "S_6") (pintype "passive"))
      (node (ref "IC1") (pin "45") (pinfunction "P0.26_45") (pintype "bidirectional"))
      (node (ref "R27") (pin "1") (pinfunction "1_1") (pintype "passive"))
    )
    (net (code "84") (name "P27") (class "Default")
      (node (ref "C41") (pin "1") (pinfunction "1_1") (pintype "passive"))
      (node (ref "EXP1") (pin "5") (pinfunction "S_5") (pintype "passive"))
      (node (ref "IC1") (pin "46") (pinfunction "P0.27_46") (pintype "bidirectional"))
      (node (ref "R28") (pin "1") (pinfunction "1_1") (pintype "passive"))
    )
    (net (code "85") (name "P28") (class "Default")
      (node (ref "IC1") (pin "47") (pinfunction "P0.28_47") (pintype "bidirectional"))
      (node (ref "IC3") (pin "7") (pinfunction "SLEEP_7") (pintype "bidirectional"))
    )
    (net (code "86") (name "P29") (class "Default")
      (node (ref "IC1") (pin "48") (pinfunction "P0.29_48") (pintype "bidirectional"))
      (node (ref "IC3") (pin "6") (pinfunction "IN1_6") (pintype "bidirectional"))
    )
    (net (code "87") (name "P30") (class "Default")
      (node (ref "IC1") (pin "3") (pinfunction "P0.30_3") (pintype "bidirectional"))
      (node (ref "IC3") (pin "5") (pinfunction "IN2_5") (pintype "bidirectional"))
    )
    (net (code "88") (name "RESET_SW") (class "Default")
      (node (ref "C20") (pin "1") (pinfunction "1_1") (pintype "passive"))
      (node (ref "IC4") (pin "21") (pinfunction "PTB1_21") (pintype "bidirectional"))
      (node (ref "R22") (pin "1") (pinfunction "1_1") (pintype "passive"))
      (node (ref "TAST_RESET") (pin "3") (pinfunction "S_3") (pintype "passive"))
      (node (ref "TAST_RESET") (pin "4") (pinfunction "S1_4") (pintype "passive"))
    )
    (net (code "89") (name "RX") (class "Default")
      (node (ref "R27") (pin "2") (pinfunction "2_2") (pintype "passive"))
      (node (ref "SERIAL") (pin "1") (pinfunction "1_1") (pintype "bidirectional"))
    )
    (net (code "90") (name "SCK") (class "Default")
      (node (ref "IC4") (pin "30") (pinfunction "PTD5_30") (pintype "bidirectional"))
      (node (ref "IC6") (pin "6") (pinfunction "SCK_6") (pintype "bidirectional"))
    )
    (net (code "91") (name "SCL{slash}P19") (class "Default")
      (node (ref "EXP1") (pin "3") (pinfunction "S_3") (pintype "passive"))
      (node (ref "I2C") (pin "1") (pinfunction "1_1") (pintype "bidirectional"))
      (node (ref "R24") (pin "2") (pinfunction "2_2") (pintype "passive"))
      (node (ref "R26") (pin "1") (pinfunction "1_1") (pintype "passive"))
      (node (ref "U1") (pin "9") (pinfunction "SCX_9") (pintype "bidirectional"))
    )
    (net (code "92") (name "SDA{slash}P20") (class "Default")
      (node (ref "EXP1") (pin "4") (pinfunction "S_4") (pintype "passive"))
      (node (ref "I2C") (pin "2") (pinfunction "2_2") (pintype "bidirectional"))
      (node (ref "R23") (pin "2") (pinfunction "2_2") (pintype "passive"))
      (node (ref "R25") (pin "1") (pinfunction "1_1") (pintype "passive"))
      (node (ref "U1") (pin "11") (pinfunction "SDX_11") (pintype "bidirectional"))
    )
    (net (code "93") (name "SWDCLK") (class "Default")
      (node (ref "IC1") (pin "24") (pinfunction "SWDCLK_24") (pintype "bidirectional"))
      (node (ref "IC4") (pin "26") (pinfunction "PTC5/LLWU_P9_26") (pintype "bidirectional"))
      (node (ref "TP7") (pin "TP") (pinfunction "TP_TP") (pintype "input"))
    )
    (net (code "94") (name "SWDIO{slash}RESET") (class "Default")
      (node (ref "IC1") (pin "23") (pinfunction "SWDIO/NRESET_23") (pintype "bidirectional"))
      (node (ref "IC4") (pin "27") (pinfunction "PTC6/LLWU_P10_27") (pintype "bidirectional"))
      (node (ref "R37") (pin "1") (pinfunction "1_1") (pintype "passive"))
      (node (ref "TP8") (pin "TP") (pinfunction "TP_TP") (pintype "input"))
    )
    (net (code "95") (name "TO_P24") (class "Default")
      (node (ref "IC4") (pin "24") (pinfunction "PTC3/LLWU_P7_24") (pintype "bidirectional"))
      (node (ref "R39") (pin "1") (pinfunction "1_1") (pintype "passive"))
      (node (ref "TP6") (pin "TP") (pinfunction "TP_TP") (pintype "input"))
    )
    (net (code "96") (name "TO_P25") (class "Default")
      (node (ref "IC4") (pin "25") (pinfunction "PTC4/LLWU_P8_25") (pintype "bidirectional"))
      (node (ref "R38") (pin "1") (pinfunction "1_1") (pintype "passive"))
      (node (ref "TP9") (pin "TP") (pinfunction "TP_TP") (pintype "input"))
    )
    (net (code "97") (name "TX") (class "Default")
      (node (ref "R28") (pin "2") (pinfunction "2_2") (pintype "passive"))
      (node (ref "SERIAL") (pin "2") (pinfunction "2_2") (pintype "bidirectional"))
    )
    (net (code "98") (name "USB_DM") (class "Default")
      (node (ref "C40") (pin "1") (pinfunction "1_1") (pintype "passive"))
      (node (ref "IC4") (pin "4") (pinfunction "USB0_DM_4") (pintype "passive"))
      (node (ref "R46") (pin "2") (pinfunction "2_2") (pintype "passive"))
    )
    (net (code "99") (name "USB_DP") (class "Default")
      (node (ref "C39") (pin "1") (pinfunction "1_1") (pintype "passive"))
      (node (ref "IC4") (pin "3") (pinfunction "USB0_DP_3") (pintype "passive"))
      (node (ref "R47") (pin "2") (pinfunction "2_2") (pintype "passive"))
    )
    (net (code "100") (name "USB_VREG") (class "Default")
      (node (ref "C4") (pin "1") (pinfunction "1_1") (pintype "passive"))
      (node (ref "IC4") (pin "5") (pinfunction "VOUT33_5") (pintype "output"))
      (node (ref "Q4") (pin "3") (pinfunction "D_3") (pintype "passive"))
      (node (ref "R22") (pin "2") (pinfunction "2_2") (pintype "passive"))
      (node (ref "TP5") (pin "TP") (pinfunction "TP_TP") (pintype "input"))
    )
    (net (code "101") (name "VCC") (class "Default")
      (node (ref "C1") (pin "1") (pinfunction "1_1") (pintype "passive"))
      (node (ref "C15") (pin "1") (pinfunction "1_1") (pintype "passive"))
      (node (ref "C17") (pin "1") (pinfunction "1_1") (pintype "passive"))
      (node (ref "C18") (pin "1") (pinfunction "1_1") (pintype "passive"))
      (node (ref "C2") (pin "1") (pinfunction "1_1") (pintype "passive"))
      (node (ref "C24") (pin "1") (pinfunction "1_1") (pintype "passive"))
      (node (ref "C29") (pin "1") (pinfunction "1_1") (pintype "passive"))
      (node (ref "C3") (pin "+") (pinfunction "+_+") (pintype "passive"))
      (node (ref "C30") (pin "1") (pinfunction "1_1") (pintype "passive"))
      (node (ref "C31") (pin "1") (pinfunction "1_1") (pintype "passive"))
      (node (ref "C35") (pin "1") (pinfunction "1_1") (pintype "passive"))
      (node (ref "C36") (pin "1") (pinfunction "1_1") (pintype "passive"))
      (node (ref "C37") (pin "1") (pinfunction "1_1") (pintype "passive"))
      (node (ref "C38") (pin "1") (pinfunction "1_1") (pintype "passive"))
      (node (ref "C5") (pin "1") (pinfunction "1_1") (pintype "passive"))
      (node (ref "C7") (pin "1") (pinfunction "1_1") (pintype "passive"))
      (node (ref "C8") (pin "1") (pinfunction "1_1") (pintype "passive"))
      (node (ref "C9") (pin "1") (pinfunction "1_1") (pintype "passive"))
      (node (ref "D3") (pin "A") (pinfunction "A_A") (pintype "passive"))
      (node (ref "EXP1") (pin "2") (pinfunction "S_2") (pintype "passive"))
      (node (ref "EXP1") (pin "25") (pinfunction "S_25") (pintype "passive"))
      (node (ref "F1") (pin "1") (pinfunction "1_1") (pintype "passive"))
      (node (ref "I2C") (pin "3") (pinfunction "3_3") (pintype "bidirectional"))
      (node (ref "IC1") (pin "1") (pinfunction "VDD_1") (pintype "bidirectional"))
      (node (ref "IC1") (pin "12") (pinfunction "VDD_2_12") (pintype "bidirectional"))
      (node (ref "IC1") (pin "35") (pinfunction "AVDD_35") (pintype "bidirectional"))
      (node (ref "IC1") (pin "36") (pinfunction "AVDD_2_36") (pintype "bidirectional"))
      (node (ref "IC3") (pin "8") (pinfunction "VCC_8") (pintype "bidirectional"))
      (node (ref "IC4") (pin "15") (pinfunction "VDD_15") (pintype "power_in"))
      (node (ref "IC4") (pin "7") (pinfunction "VDDA_7") (pintype "power_in"))
      (node (ref "IC5") (pin "5") (pinfunction "V+_5") (pintype "power_in"))
      (node (ref "IC6") (pin "8") (pinfunction "VCC_8") (pintype "bidirectional"))
      (node (ref "LED1") (pin "2") (pinfunction "VDD_2") (pintype "power_in"))
      (node (ref "MIC1") (pin "1") (pinfunction "VDD_1") (pintype "bidirectional"))
      (node (ref "Q1") (pin "2") (pinfunction "S_2") (pintype "passive"))
      (node (ref "Q4") (pin "2") (pinfunction "S_2") (pintype "passive"))
      (node (ref "R19") (pin "2") (pinfunction "2_2") (pintype "passive"))
      (node (ref "R2") (pin "2") (pinfunction "2_2") (pintype "passive"))
      (node (ref "R20") (pin "2") (pinfunction "2_2") (pintype "passive"))
      (node (ref "R25") (pin "2") (pinfunction "2_2") (pintype "passive"))
      (node (ref "R26") (pin "2") (pinfunction "2_2") (pintype "passive"))
      (node (ref "R3") (pin "2") (pinfunction "2_2") (pintype "passive"))
      (node (ref "R30") (pin "2") (pinfunction "2_2") (pintype "passive"))
      (node (ref "R33") (pin "2") (pinfunction "2_2") (pintype "passive"))
      (node (ref "R34") (pin "2") (pinfunction "2_2") (pintype "passive"))
      (node (ref "R37") (pin "2") (pinfunction "2_2") (pintype "passive"))
      (node (ref "R42") (pin "2") (pinfunction "2_2") (pintype "passive"))
      (node (ref "R48") (pin "2") (pinfunction "2_2") (pintype "passive"))
      (node (ref "R6") (pin "2") (pinfunction "2_2") (pintype "passive"))
      (node (ref "R7") (pin "2") (pinfunction "2_2") (pintype "passive"))
      (node (ref "SERIAL") (pin "3") (pinfunction "3_3") (pintype "bidirectional"))
      (node (ref "U1") (pin "13") (pinfunction "VDDIO_13") (pintype "bidirectional"))
      (node (ref "U1") (pin "3") (pinfunction "VDD_3") (pintype "bidirectional"))
      (node (ref "U1") (pin "7") (pinfunction "PS_7") (pintype "bidirectional"))
    )
    (net (code "102") (name "VM") (class "Default")
      (node (ref "C16") (pin "1") (pinfunction "1_1") (pintype "passive"))
      (node (ref "C26") (pin "1") (pinfunction "1_1") (pintype "passive"))
      (node (ref "D3") (pin "C") (pinfunction "C_C") (pintype "passive"))
      (node (ref "IC3") (pin "1") (pinfunction "VM_1") (pintype "bidirectional"))
      (node (ref "JP1") (pin "5") (pinfunction "5_5") (pintype "passive"))
    )
    (net (code "103") (name "unconnected-(IC1-DCC-Pad2)") (class "Default")
      (node (ref "IC1") (pin "2") (pinfunction "DCC_2") (pintype "bidirectional"))
    )
    (net (code "104") (name "unconnected-(IC4-PTA1-Pad11)") (class "Default")
      (node (ref "IC4") (pin "11") (pinfunction "PTA1_11") (pintype "bidirectional"))
    )
    (net (code "105") (name "unconnected-(IC4-PTA2-Pad12)") (class "Default")
      (node (ref "IC4") (pin "12") (pinfunction "PTA2_12") (pintype "bidirectional"))
    )
    (net (code "106") (name "unconnected-(IC4-PTE0-Pad1)") (class "Default")
      (node (ref "IC4") (pin "1") (pinfunction "PTE0_1") (pintype "bidirectional"))
    )
    (net (code "107") (name "unconnected-(IC4-PTE30-Pad9)") (class "Default")
      (node (ref "IC4") (pin "9") (pinfunction "PTE30_9") (pintype "bidirectional"))
    )
    (net (code "108") (name "unconnected-(LED1-DO-Pad3)") (class "Default")
      (node (ref "LED1") (pin "3") (pinfunction "DO_3") (pintype "output"))
    )
    (net (code "109") (name "unconnected-(U1-CSB1-Pad16)") (class "Default")
      (node (ref "U1") (pin "16") (pinfunction "CSB1_16") (pintype "bidirectional"))
    )
    (net (code "110") (name "unconnected-(U1-CSB2-Pad5)") (class "Default")
      (node (ref "U1") (pin "5") (pinfunction "CSB2_5") (pintype "bidirectional"))
    )
    (net (code "111") (name "unconnected-(U1-INT2-Pad1)") (class "Default")
      (node (ref "U1") (pin "1") (pinfunction "INT2_1") (pintype "bidirectional"))
    )
    (net (code "112") (name "unconnected-(U1-INT4-Pad15)") (class "Default")
      (node (ref "U1") (pin "15") (pinfunction "INT4_15") (pintype "bidirectional"))
    )
    (net (code "113") (name "unconnected-(U1-INT5-Pad10)") (class "Default")
      (node (ref "U1") (pin "10") (pinfunction "INT5_10") (pintype "bidirectional"))
    )
    (net (code "114") (name "unconnected-(U1-N{slash}C-Pad8)") (class "Default")
      (node (ref "U1") (pin "8") (pinfunction "N/C_8") (pintype "bidirectional"))
    )
    (net (code "115") (name "unconnected-(U1-N{slash}C-Pad18)") (class "Default")
      (node (ref "U1") (pin "18") (pinfunction "N/C_18") (pintype "bidirectional"))
    )
    (net (code "116") (name "unconnected-(USB2-Pad4)") (class "Default")
      (node (ref "USB2") (pin "4") (pinfunction "4_4") (pintype "bidirectional"))
    )
  )
)
